# skematik_jppi.net
KiCad netlist of a schematic drawn in EAGLE
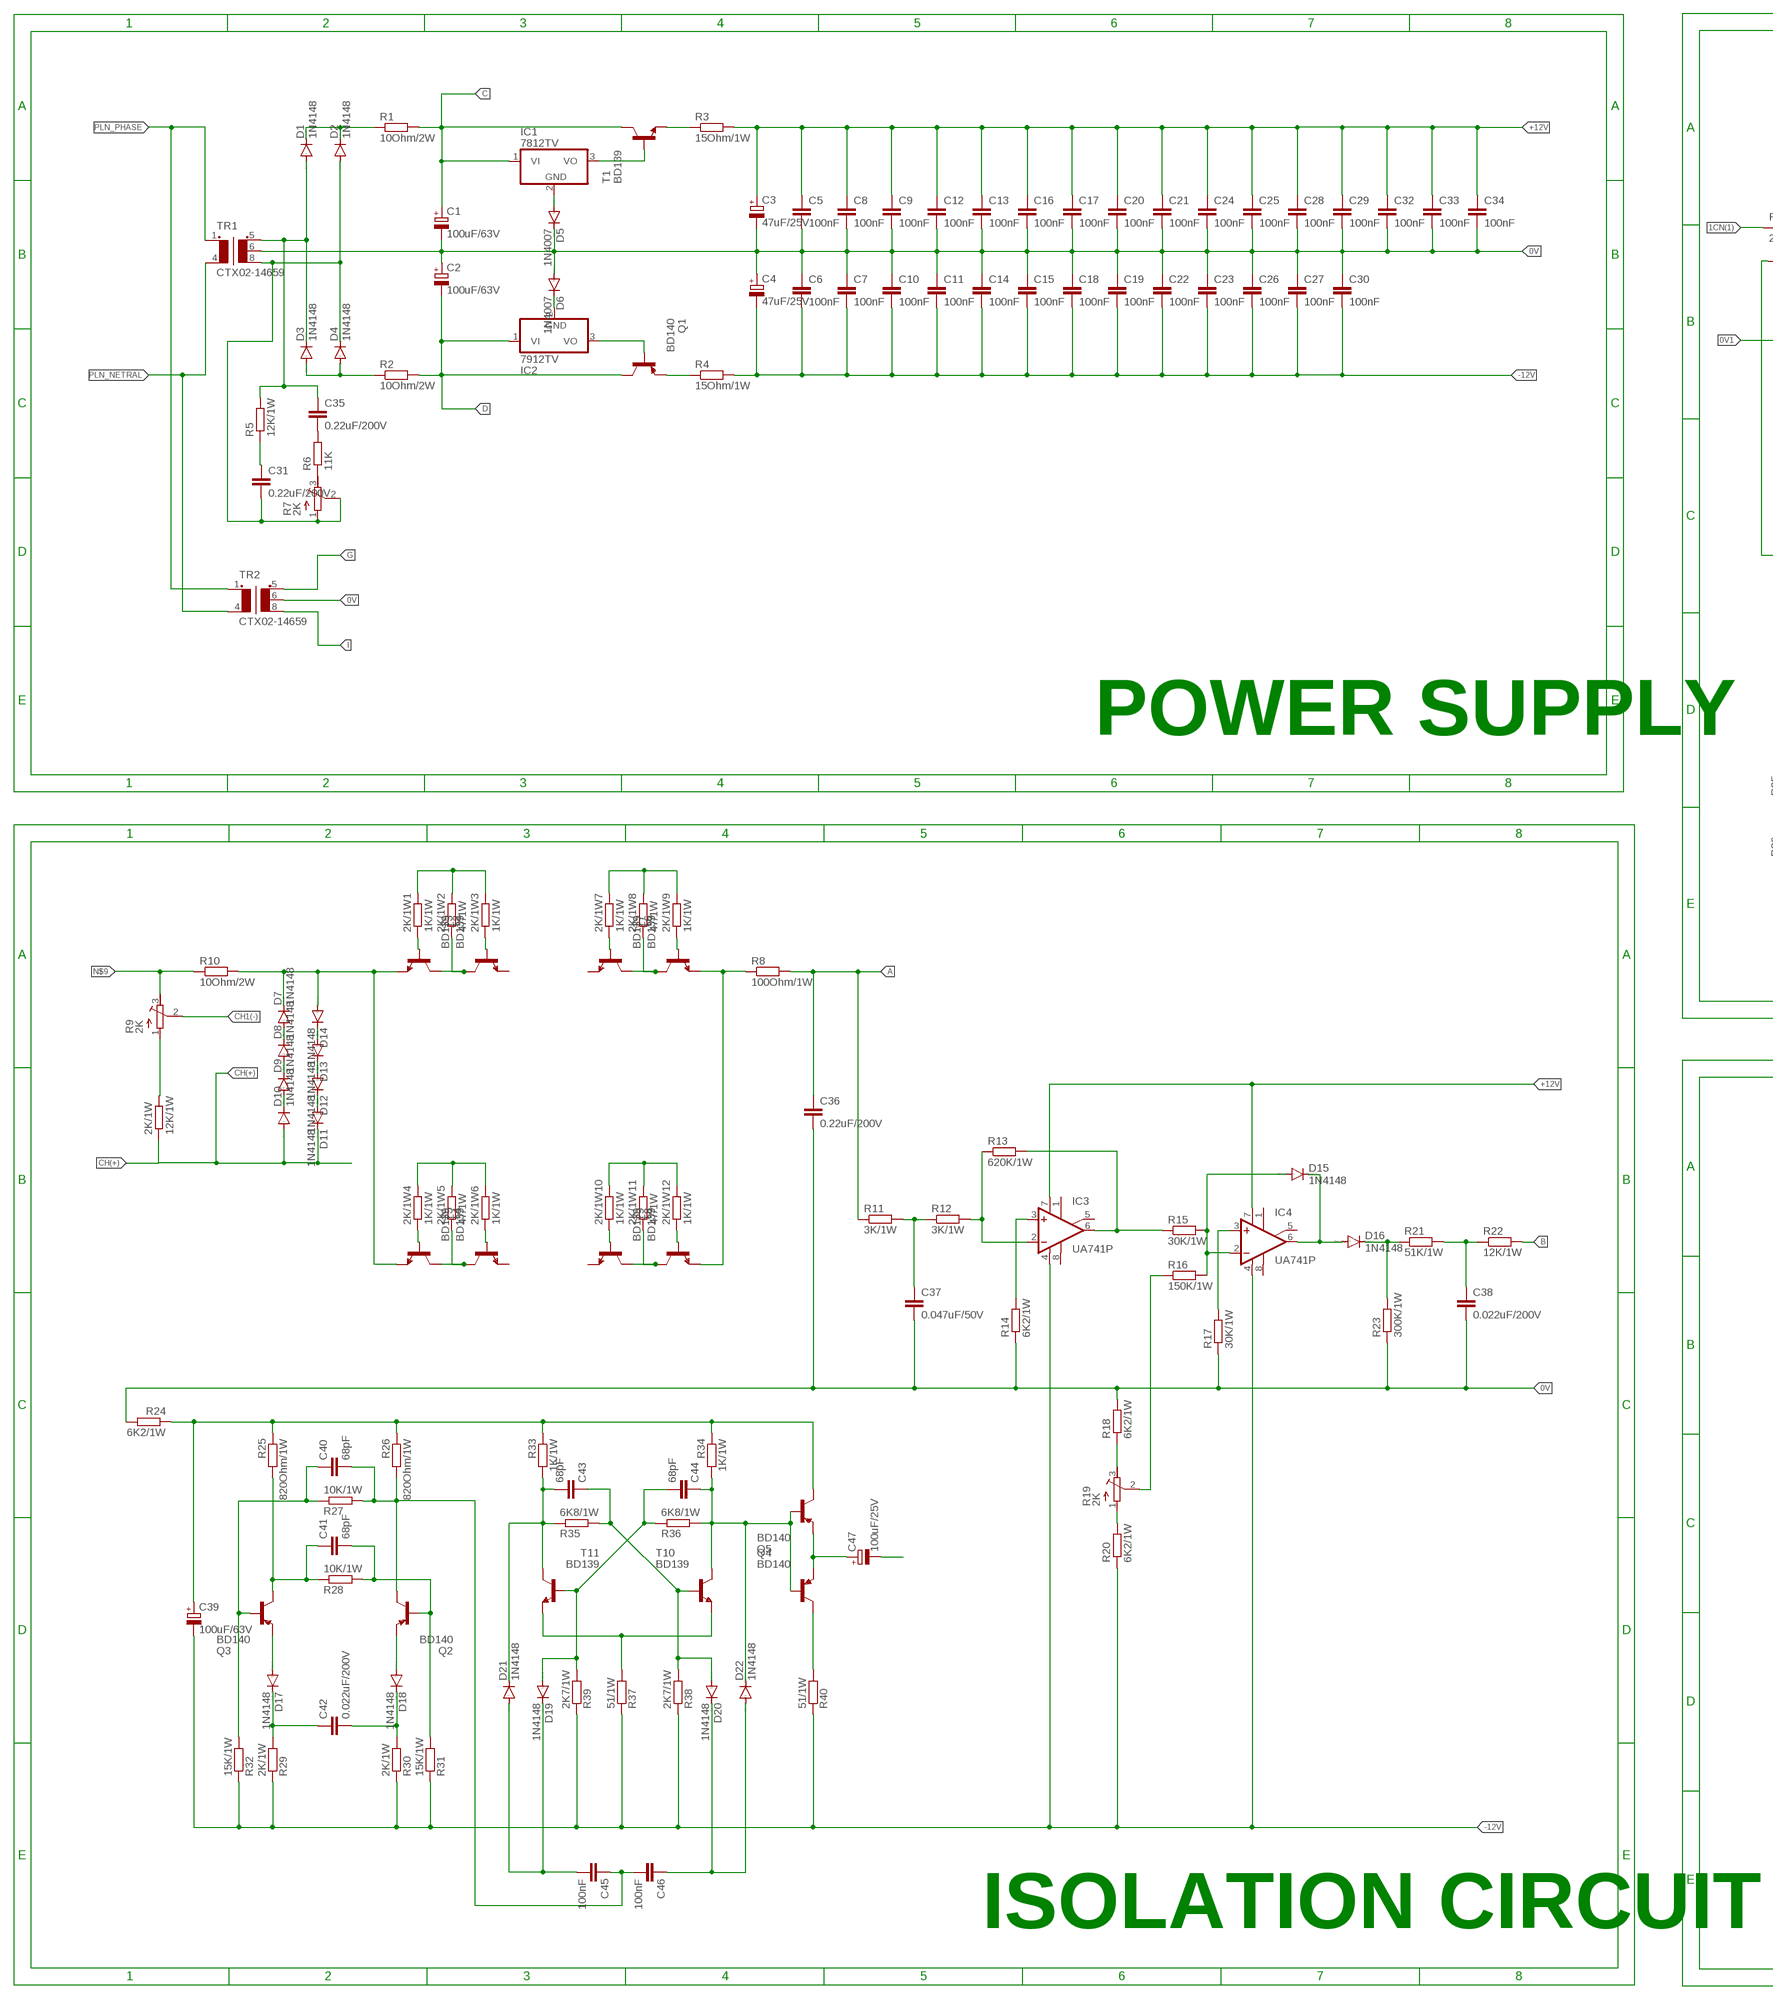
[diagram p0: schematic, sheet 1, part 1 of 3]
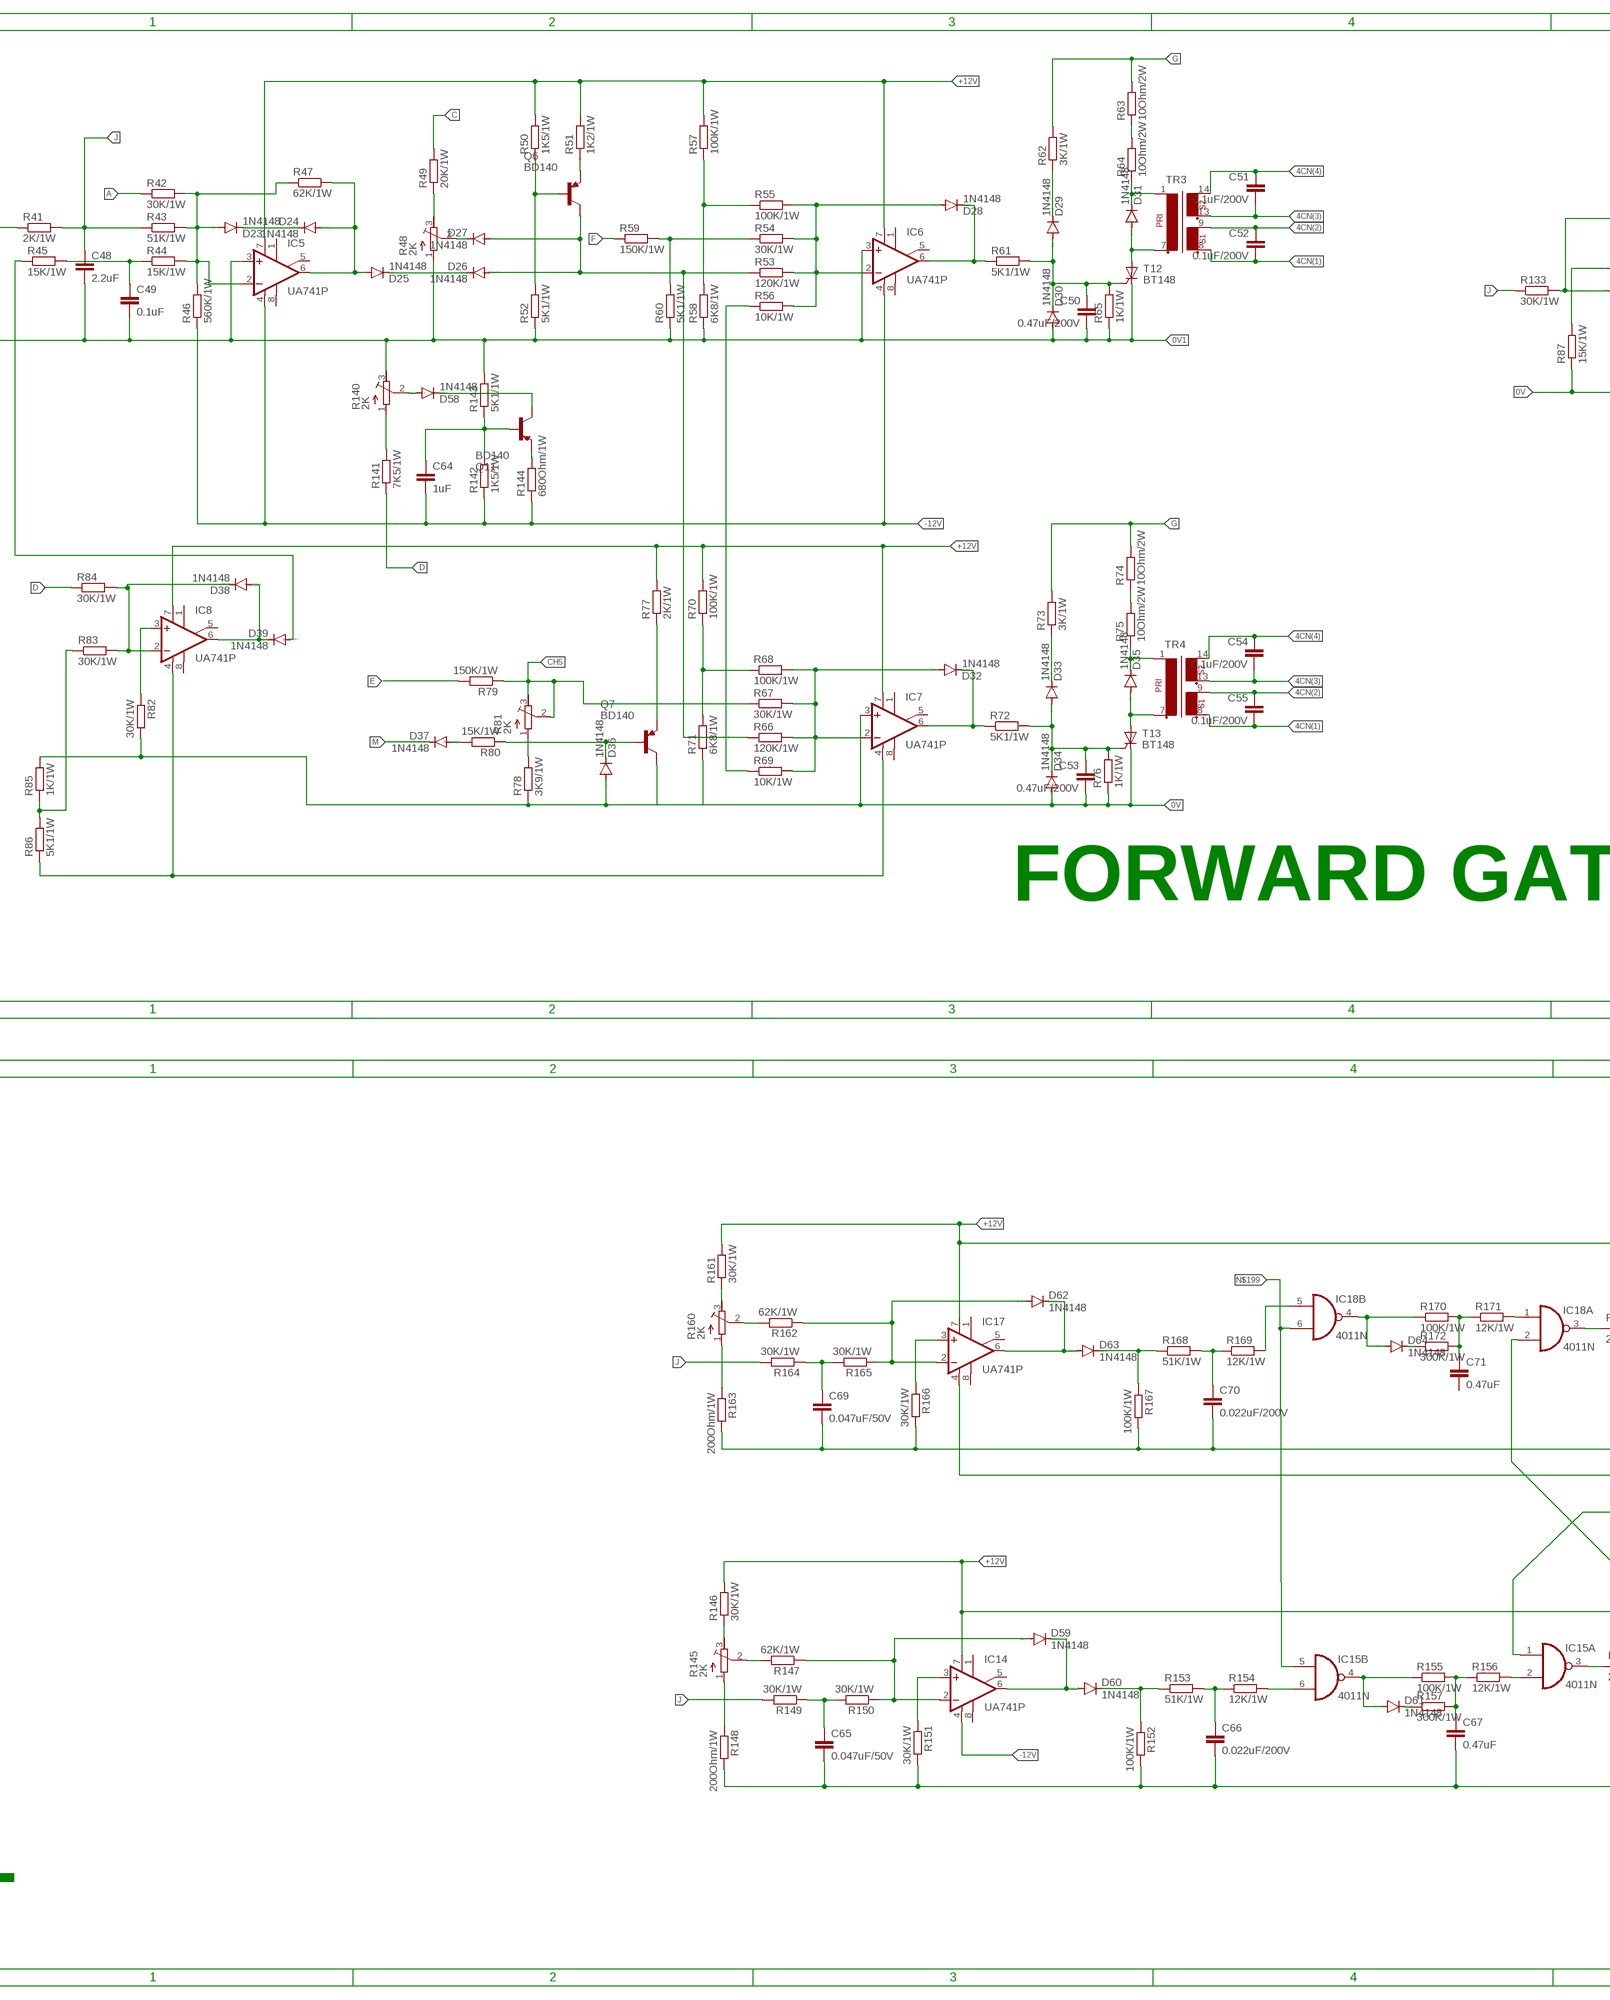
[diagram p1: schematic, sheet 1, part 2 of 3]
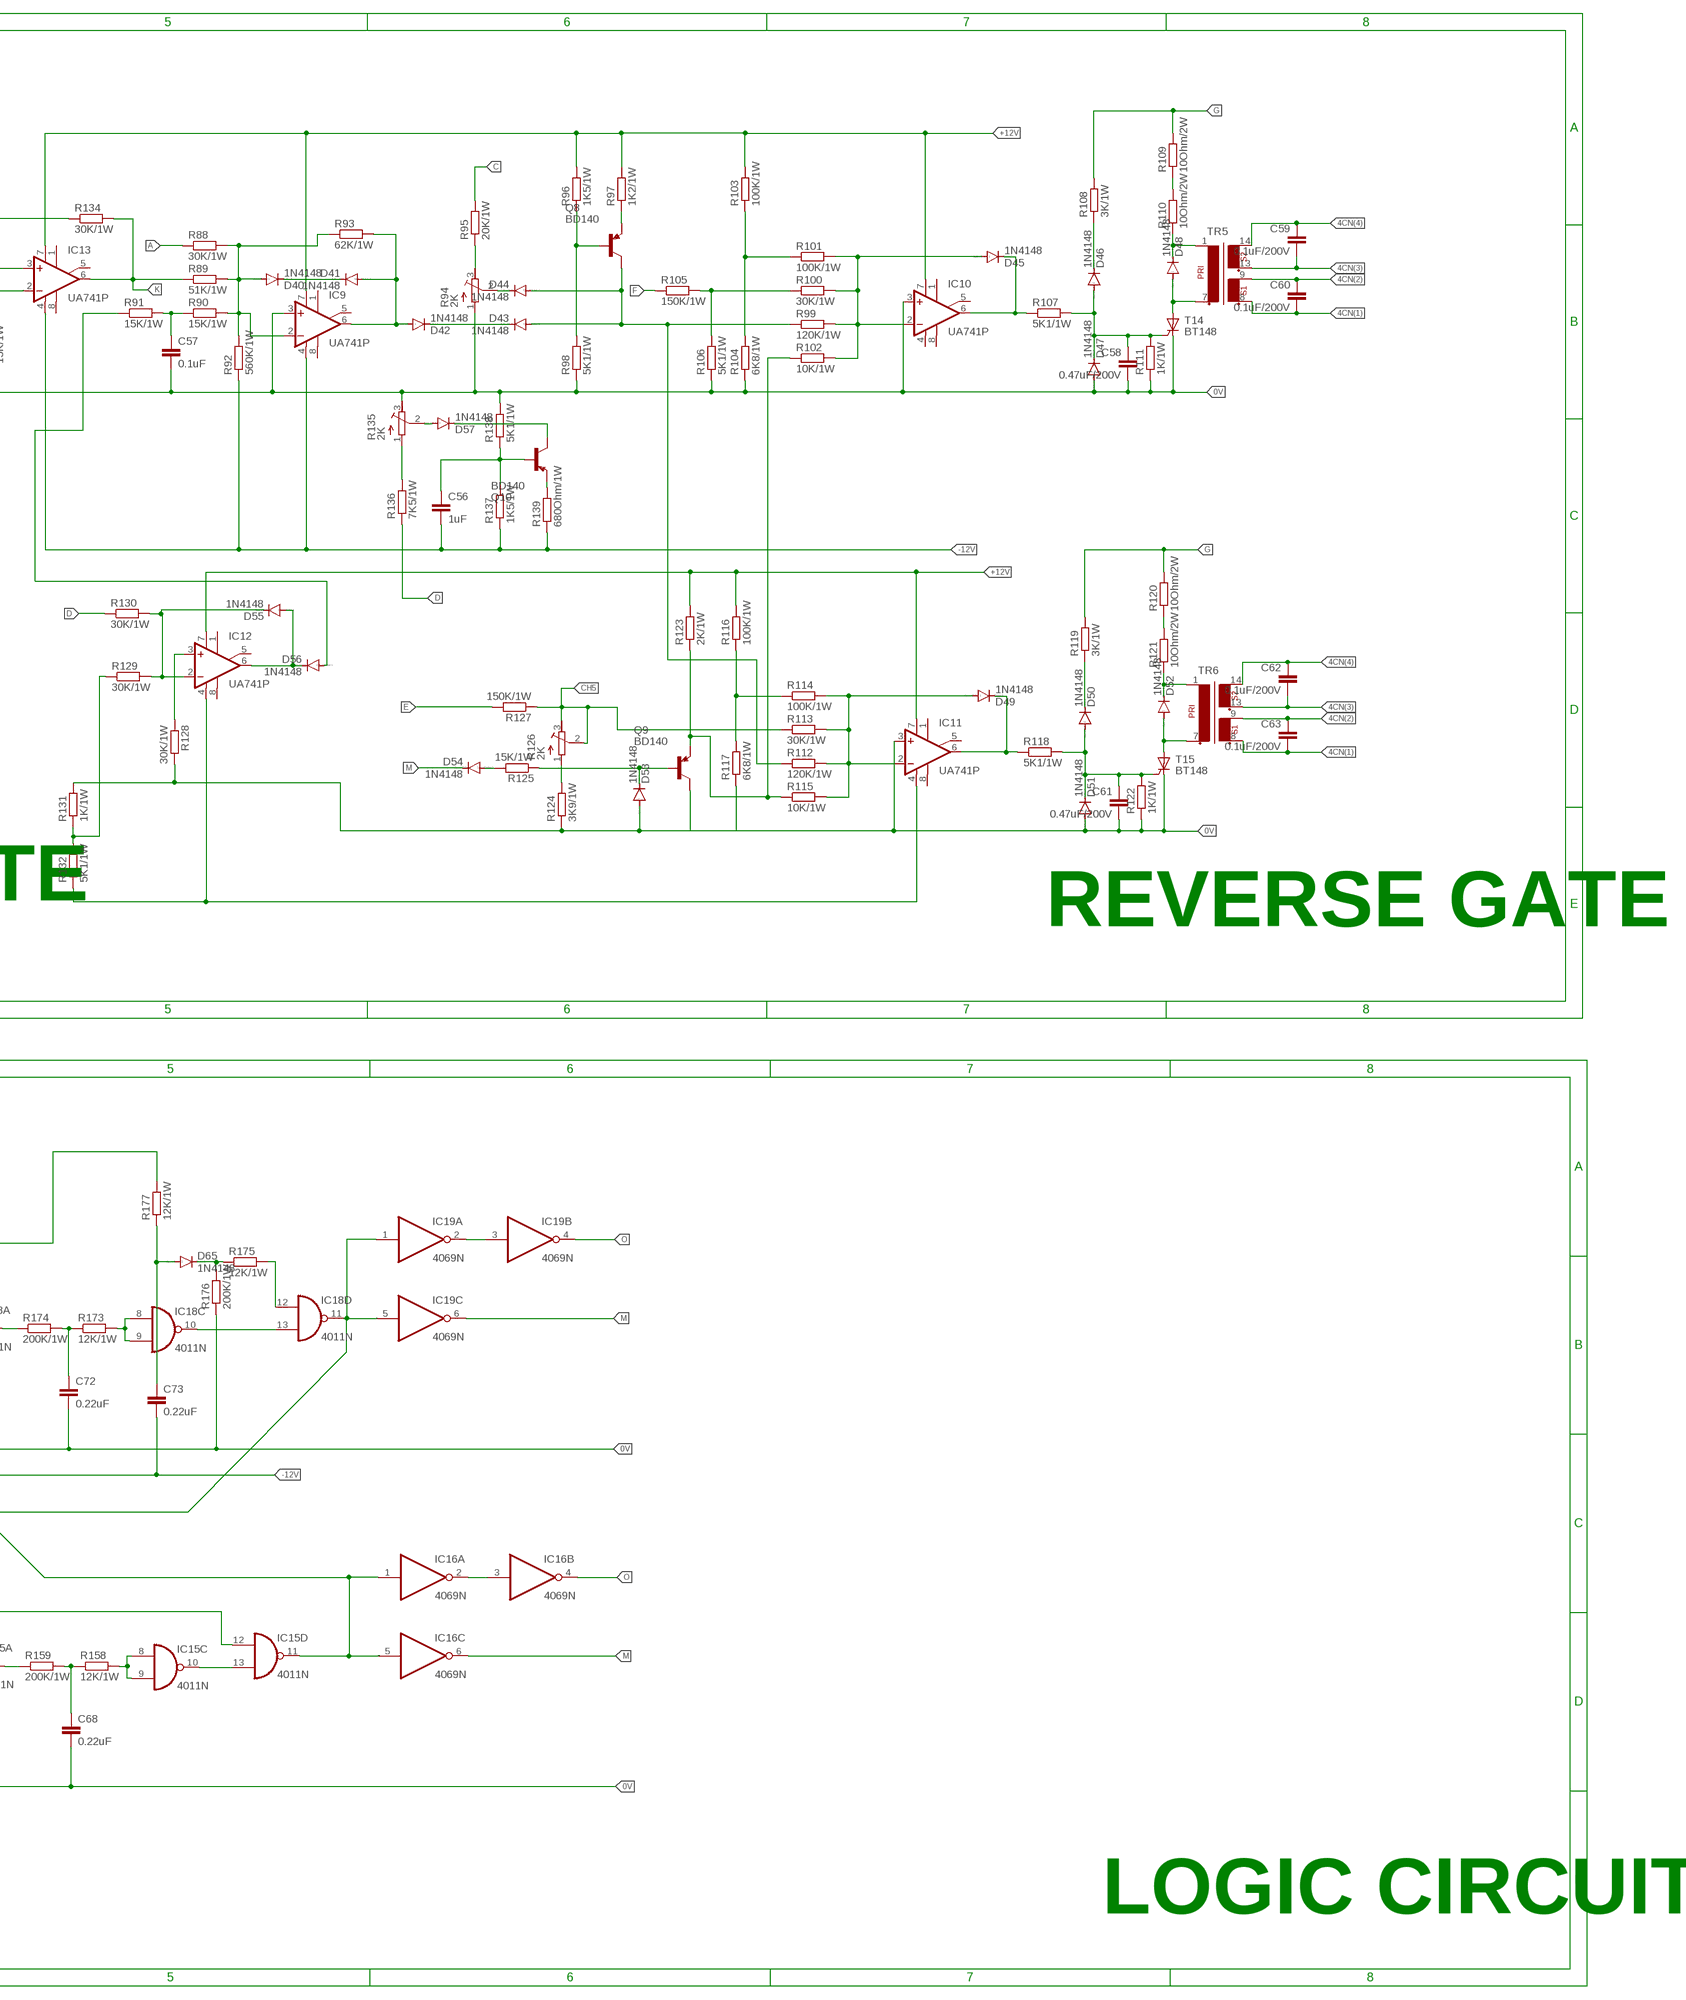
[diagram p2: schematic, sheet 1, part 3 of 3]

(export (version "E")
  (design (tool "Eeschema 10.0.6"))
  (components
    (comp (ref "2K/1W")
      (value "12K/1W")
      (footprint "eagle-import:0309_12")
      (libsource (lib "eagle-import") (part "R-EU_0309/12"))
    )
    (comp (ref "2K/1W1")
      (value "1K/1W")
      (footprint "eagle-import:0309_12")
      (libsource (lib "eagle-import") (part "R-EU_0309/12"))
    )
    (comp (ref "2K/1W2")
      (value "47/1W")
      (footprint "eagle-import:0309_12")
      (libsource (lib "eagle-import") (part "R-EU_0309/12"))
    )
    (comp (ref "2K/1W3")
      (value "1K/1W")
      (footprint "eagle-import:0309_12")
      (libsource (lib "eagle-import") (part "R-EU_0309/12"))
    )
    (comp (ref "2K/1W4")
      (value "1K/1W")
      (footprint "eagle-import:0309_12")
      (libsource (lib "eagle-import") (part "R-EU_0309/12"))
    )
    (comp (ref "2K/1W5")
      (value "47/1W")
      (footprint "eagle-import:0309_12")
      (libsource (lib "eagle-import") (part "R-EU_0309/12"))
    )
    (comp (ref "2K/1W6")
      (value "1K/1W")
      (footprint "eagle-import:0309_12")
      (libsource (lib "eagle-import") (part "R-EU_0309/12"))
    )
    (comp (ref "2K/1W7")
      (value "1K/1W")
      (footprint "eagle-import:0309_12")
      (libsource (lib "eagle-import") (part "R-EU_0309/12"))
    )
    (comp (ref "2K/1W8")
      (value "47/1W")
      (footprint "eagle-import:0309_12")
      (libsource (lib "eagle-import") (part "R-EU_0309/12"))
    )
    (comp (ref "2K/1W9")
      (value "1K/1W")
      (footprint "eagle-import:0309_12")
      (libsource (lib "eagle-import") (part "R-EU_0309/12"))
    )
    (comp (ref "2K/1W10")
      (value "1K/1W")
      (footprint "eagle-import:0309_12")
      (libsource (lib "eagle-import") (part "R-EU_0309/12"))
    )
    (comp (ref "2K/1W11")
      (value "47/1W")
      (footprint "eagle-import:0309_12")
      (libsource (lib "eagle-import") (part "R-EU_0309/12"))
    )
    (comp (ref "2K/1W12")
      (value "1K/1W")
      (footprint "eagle-import:0309_12")
      (libsource (lib "eagle-import") (part "R-EU_0309/12"))
    )
    (comp (ref "C1")
      (value "100uF/63V")
      (footprint "eagle-import:E5-10,5")
      (libsource (lib "eagle-import") (part "CPOL-EUE5-10.5"))
    )
    (comp (ref "C2")
      (value "100uF/63V")
      (footprint "eagle-import:E5-10,5")
      (libsource (lib "eagle-import") (part "CPOL-EUE5-10.5"))
    )
    (comp (ref "C3")
      (value "47uF/25V")
      (footprint "eagle-import:E5-10,5")
      (libsource (lib "eagle-import") (part "CPOL-EUE5-10.5"))
    )
    (comp (ref "C4")
      (value "47uF/25V")
      (footprint "eagle-import:E5-10,5")
      (libsource (lib "eagle-import") (part "CPOL-EUE5-10.5"))
    )
    (comp (ref "C5")
      (value "100nF")
      (footprint "eagle-import:C050-025X075")
      (libsource (lib "eagle-import") (part "C-EU050-025X075"))
    )
    (comp (ref "C6")
      (value "100nF")
      (footprint "eagle-import:C050-025X075")
      (libsource (lib "eagle-import") (part "C-EU050-025X075"))
    )
    (comp (ref "C7")
      (value "100nF")
      (footprint "eagle-import:C050-025X075")
      (libsource (lib "eagle-import") (part "C-EU050-025X075"))
    )
    (comp (ref "C8")
      (value "100nF")
      (footprint "eagle-import:C050-025X075")
      (libsource (lib "eagle-import") (part "C-EU050-025X075"))
    )
    (comp (ref "C9")
      (value "100nF")
      (footprint "eagle-import:C050-025X075")
      (libsource (lib "eagle-import") (part "C-EU050-025X075"))
    )
    (comp (ref "C10")
      (value "100nF")
      (footprint "eagle-import:C050-025X075")
      (libsource (lib "eagle-import") (part "C-EU050-025X075"))
    )
    (comp (ref "C11")
      (value "100nF")
      (footprint "eagle-import:C050-025X075")
      (libsource (lib "eagle-import") (part "C-EU050-025X075"))
    )
    (comp (ref "C12")
      (value "100nF")
      (footprint "eagle-import:C050-025X075")
      (libsource (lib "eagle-import") (part "C-EU050-025X075"))
    )
    (comp (ref "C13")
      (value "100nF")
      (footprint "eagle-import:C050-025X075")
      (libsource (lib "eagle-import") (part "C-EU050-025X075"))
    )
    (comp (ref "C14")
      (value "100nF")
      (footprint "eagle-import:C050-025X075")
      (libsource (lib "eagle-import") (part "C-EU050-025X075"))
    )
    (comp (ref "C15")
      (value "100nF")
      (footprint "eagle-import:C050-025X075")
      (libsource (lib "eagle-import") (part "C-EU050-025X075"))
    )
    (comp (ref "C16")
      (value "100nF")
      (footprint "eagle-import:C050-025X075")
      (libsource (lib "eagle-import") (part "C-EU050-025X075"))
    )
    (comp (ref "C17")
      (value "100nF")
      (footprint "eagle-import:C050-025X075")
      (libsource (lib "eagle-import") (part "C-EU050-025X075"))
    )
    (comp (ref "C18")
      (value "100nF")
      (footprint "eagle-import:C050-025X075")
      (libsource (lib "eagle-import") (part "C-EU050-025X075"))
    )
    (comp (ref "C19")
      (value "100nF")
      (footprint "eagle-import:C050-025X075")
      (libsource (lib "eagle-import") (part "C-EU050-025X075"))
    )
    (comp (ref "C20")
      (value "100nF")
      (footprint "eagle-import:C050-025X075")
      (libsource (lib "eagle-import") (part "C-EU050-025X075"))
    )
    (comp (ref "C21")
      (value "100nF")
      (footprint "eagle-import:C050-025X075")
      (libsource (lib "eagle-import") (part "C-EU050-025X075"))
    )
    (comp (ref "C22")
      (value "100nF")
      (footprint "eagle-import:C050-025X075")
      (libsource (lib "eagle-import") (part "C-EU050-025X075"))
    )
    (comp (ref "C23")
      (value "100nF")
      (footprint "eagle-import:C050-025X075")
      (libsource (lib "eagle-import") (part "C-EU050-025X075"))
    )
    (comp (ref "C24")
      (value "100nF")
      (footprint "eagle-import:C050-025X075")
      (libsource (lib "eagle-import") (part "C-EU050-025X075"))
    )
    (comp (ref "C25")
      (value "100nF")
      (footprint "eagle-import:C050-025X075")
      (libsource (lib "eagle-import") (part "C-EU050-025X075"))
    )
    (comp (ref "C26")
      (value "100nF")
      (footprint "eagle-import:C050-025X075")
      (libsource (lib "eagle-import") (part "C-EU050-025X075"))
    )
    (comp (ref "C27")
      (value "100nF")
      (footprint "eagle-import:C050-025X075")
      (libsource (lib "eagle-import") (part "C-EU050-025X075"))
    )
    (comp (ref "C28")
      (value "100nF")
      (footprint "eagle-import:C050-025X075")
      (libsource (lib "eagle-import") (part "C-EU050-025X075"))
    )
    (comp (ref "C29")
      (value "100nF")
      (footprint "eagle-import:C050-025X075")
      (libsource (lib "eagle-import") (part "C-EU050-025X075"))
    )
    (comp (ref "C30")
      (value "100nF")
      (footprint "eagle-import:C050-025X075")
      (libsource (lib "eagle-import") (part "C-EU050-025X075"))
    )
    (comp (ref "C31")
      (value "0.22uF/200V")
      (footprint "eagle-import:C102-043X133")
      (libsource (lib "eagle-import") (part "C-EU102-043X133"))
    )
    (comp (ref "C32")
      (value "100nF")
      (footprint "eagle-import:C050-025X075")
      (libsource (lib "eagle-import") (part "C-EU050-025X075"))
    )
    (comp (ref "C33")
      (value "100nF")
      (footprint "eagle-import:C050-025X075")
      (libsource (lib "eagle-import") (part "C-EU050-025X075"))
    )
    (comp (ref "C34")
      (value "100nF")
      (footprint "eagle-import:C050-025X075")
      (libsource (lib "eagle-import") (part "C-EU050-025X075"))
    )
    (comp (ref "C35")
      (value "0.22uF/200V")
      (footprint "eagle-import:C102-043X133")
      (libsource (lib "eagle-import") (part "C-EU102-043X133"))
    )
    (comp (ref "C36")
      (value "0.22uF/200V")
      (footprint "eagle-import:C102-043X133")
      (libsource (lib "eagle-import") (part "C-EU102-043X133"))
    )
    (comp (ref "C37")
      (value "0.047uF/50V")
      (footprint "eagle-import:C075-032X103")
      (libsource (lib "eagle-import") (part "C-EU075-032X103"))
    )
    (comp (ref "C38")
      (value "0.022uF/200V")
      (footprint "eagle-import:C102-043X133")
      (libsource (lib "eagle-import") (part "C-EU102-043X133"))
    )
    (comp (ref "C39")
      (value "100uF/63V")
      (footprint "eagle-import:E5-10,5")
      (libsource (lib "eagle-import") (part "CPOL-EUE5-10.5"))
    )
    (comp (ref "C40")
      (value "68pF")
      (footprint "eagle-import:C050-024X044")
      (libsource (lib "eagle-import") (part "C-EU050-024X044"))
    )
    (comp (ref "C41")
      (value "68pF")
      (footprint "eagle-import:C050-024X044")
      (libsource (lib "eagle-import") (part "C-EU050-024X044"))
    )
    (comp (ref "C42")
      (value "0.022uF/200V")
      (footprint "eagle-import:C102-043X133")
      (libsource (lib "eagle-import") (part "C-EU102-043X133"))
    )
    (comp (ref "C43")
      (value "68pF")
      (footprint "eagle-import:C050-024X044")
      (libsource (lib "eagle-import") (part "C-EU050-024X044"))
    )
    (comp (ref "C44")
      (value "68pF")
      (footprint "eagle-import:C050-024X044")
      (libsource (lib "eagle-import") (part "C-EU050-024X044"))
    )
    (comp (ref "C45")
      (value "100nF")
      (footprint "eagle-import:C050-025X075")
      (libsource (lib "eagle-import") (part "C-EU050-025X075"))
    )
    (comp (ref "C46")
      (value "100nF")
      (footprint "eagle-import:C050-025X075")
      (libsource (lib "eagle-import") (part "C-EU050-025X075"))
    )
    (comp (ref "C47")
      (value "100uF/25V")
      (footprint "eagle-import:E5-10,5")
      (libsource (lib "eagle-import") (part "CPOL-EUE5-10.5"))
    )
    (comp (ref "C48")
      (value "2.2uF")
      (footprint "eagle-import:C050-025X075")
      (libsource (lib "eagle-import") (part "C-EU050-025X075"))
    )
    (comp (ref "C49")
      (value "0.1uF")
      (footprint "eagle-import:C050-025X075")
      (libsource (lib "eagle-import") (part "C-EU050-025X075"))
    )
    (comp (ref "C50")
      (value "0.47uF/200V")
      (footprint "eagle-import:C102-043X133")
      (libsource (lib "eagle-import") (part "C-EU102-043X133"))
    )
    (comp (ref "C51")
      (value "0.1uF/200V")
      (footprint "eagle-import:C102-043X133")
      (libsource (lib "eagle-import") (part "C-EU102-043X133"))
    )
    (comp (ref "C52")
      (value "0.1uF/200V")
      (footprint "eagle-import:C102-043X133")
      (libsource (lib "eagle-import") (part "C-EU102-043X133"))
    )
    (comp (ref "C53")
      (value "0.47uF/200V")
      (footprint "eagle-import:C102-043X133")
      (libsource (lib "eagle-import") (part "C-EU102-043X133"))
    )
    (comp (ref "C54")
      (value "0.1uF/200V")
      (footprint "eagle-import:C102-043X133")
      (libsource (lib "eagle-import") (part "C-EU102-043X133"))
    )
    (comp (ref "C55")
      (value "0.1uF/200V")
      (footprint "eagle-import:C102-043X133")
      (libsource (lib "eagle-import") (part "C-EU102-043X133"))
    )
    (comp (ref "C56")
      (value "1uF")
      (footprint "eagle-import:C050-025X075")
      (libsource (lib "eagle-import") (part "C-EU050-025X075"))
    )
    (comp (ref "C57")
      (value "0.1uF")
      (footprint "eagle-import:C050-025X075")
      (libsource (lib "eagle-import") (part "C-EU050-025X075"))
    )
    (comp (ref "C58")
      (value "0.47uF/200V")
      (footprint "eagle-import:C102-043X133")
      (libsource (lib "eagle-import") (part "C-EU102-043X133"))
    )
    (comp (ref "C59")
      (value "0.1uF/200V")
      (footprint "eagle-import:C102-043X133")
      (libsource (lib "eagle-import") (part "C-EU102-043X133"))
    )
    (comp (ref "C60")
      (value "0.1uF/200V")
      (footprint "eagle-import:C102-043X133")
      (libsource (lib "eagle-import") (part "C-EU102-043X133"))
    )
    (comp (ref "C61")
      (value "0.47uF/200V")
      (footprint "eagle-import:C102-043X133")
      (libsource (lib "eagle-import") (part "C-EU102-043X133"))
    )
    (comp (ref "C62")
      (value "0.1uF/200V")
      (footprint "eagle-import:C102-043X133")
      (libsource (lib "eagle-import") (part "C-EU102-043X133"))
    )
    (comp (ref "C63")
      (value "0.1uF/200V")
      (footprint "eagle-import:C102-043X133")
      (libsource (lib "eagle-import") (part "C-EU102-043X133"))
    )
    (comp (ref "C64")
      (value "1uF")
      (footprint "eagle-import:C050-025X075")
      (libsource (lib "eagle-import") (part "C-EU050-025X075"))
    )
    (comp (ref "C65")
      (value "0.047uF/50V")
      (footprint "eagle-import:C102-043X133")
      (libsource (lib "eagle-import") (part "C-EU102-043X133"))
    )
    (comp (ref "C66")
      (value "0.022uF/200V")
      (footprint "eagle-import:C102-043X133")
      (libsource (lib "eagle-import") (part "C-EU102-043X133"))
    )
    (comp (ref "C67")
      (value "0.47uF")
      (footprint "eagle-import:C102-043X133")
      (libsource (lib "eagle-import") (part "C-EU102-043X133"))
    )
    (comp (ref "C68")
      (value "0.22uF")
      (footprint "eagle-import:C102-043X133")
      (libsource (lib "eagle-import") (part "C-EU102-043X133"))
    )
    (comp (ref "C69")
      (value "0.047uF/50V")
      (footprint "eagle-import:C102-043X133")
      (libsource (lib "eagle-import") (part "C-EU102-043X133"))
    )
    (comp (ref "C70")
      (value "0.022uF/200V")
      (footprint "eagle-import:C102-043X133")
      (libsource (lib "eagle-import") (part "C-EU102-043X133"))
    )
    (comp (ref "C71")
      (value "0.47uF")
      (footprint "eagle-import:C102-043X133")
      (libsource (lib "eagle-import") (part "C-EU102-043X133"))
    )
    (comp (ref "C72")
      (value "0.22uF")
      (footprint "eagle-import:C102-043X133")
      (libsource (lib "eagle-import") (part "C-EU102-043X133"))
    )
    (comp (ref "C73")
      (value "0.22uF")
      (footprint "eagle-import:C102-043X133")
      (libsource (lib "eagle-import") (part "C-EU102-043X133"))
    )
    (comp (ref "D1")
      (value "1N4148")
      (footprint "eagle-import:DO41-10")
      (libsource (lib "eagle-import") (part "1N4004"))
    )
    (comp (ref "D2")
      (value "1N4148")
      (footprint "eagle-import:DO41-10")
      (libsource (lib "eagle-import") (part "1N4004"))
    )
    (comp (ref "D3")
      (value "1N4148")
      (footprint "eagle-import:DO41-10")
      (libsource (lib "eagle-import") (part "1N4004"))
    )
    (comp (ref "D4")
      (value "1N4148")
      (footprint "eagle-import:DO41-10")
      (libsource (lib "eagle-import") (part "1N4004"))
    )
    (comp (ref "D5")
      (value "1N4007")
      (footprint "eagle-import:DO41-10")
      (libsource (lib "eagle-import") (part "1N4004"))
    )
    (comp (ref "D6")
      (value "1N4007")
      (footprint "eagle-import:DO41-10")
      (libsource (lib "eagle-import") (part "1N4004"))
    )
    (comp (ref "D7")
      (value "1N4148")
      (footprint "eagle-import:DO41-10")
      (libsource (lib "eagle-import") (part "1N4004"))
    )
    (comp (ref "D8")
      (value "1N4148")
      (footprint "eagle-import:DO41-10")
      (libsource (lib "eagle-import") (part "1N4004"))
    )
    (comp (ref "D9")
      (value "1N4148")
      (footprint "eagle-import:DO41-10")
      (libsource (lib "eagle-import") (part "1N4004"))
    )
    (comp (ref "D10")
      (value "1N4148")
      (footprint "eagle-import:DO41-10")
      (libsource (lib "eagle-import") (part "1N4004"))
    )
    (comp (ref "D11")
      (value "1N4148")
      (footprint "eagle-import:DO41-10")
      (libsource (lib "eagle-import") (part "1N4004"))
    )
    (comp (ref "D12")
      (value "1N4148")
      (footprint "eagle-import:DO41-10")
      (libsource (lib "eagle-import") (part "1N4004"))
    )
    (comp (ref "D13")
      (value "1N4148")
      (footprint "eagle-import:DO41-10")
      (libsource (lib "eagle-import") (part "1N4004"))
    )
    (comp (ref "D14")
      (value "1N4148")
      (footprint "eagle-import:DO41-10")
      (libsource (lib "eagle-import") (part "1N4004"))
    )
    (comp (ref "D15")
      (value "1N4148")
      (footprint "eagle-import:DO41-10")
      (libsource (lib "eagle-import") (part "1N4004"))
    )
    (comp (ref "D16")
      (value "1N4148")
      (footprint "eagle-import:DO41-10")
      (libsource (lib "eagle-import") (part "1N4004"))
    )
    (comp (ref "D17")
      (value "1N4148")
      (footprint "eagle-import:DO41-10")
      (libsource (lib "eagle-import") (part "1N4004"))
    )
    (comp (ref "D18")
      (value "1N4148")
      (footprint "eagle-import:DO41-10")
      (libsource (lib "eagle-import") (part "1N4004"))
    )
    (comp (ref "D19")
      (value "1N4148")
      (footprint "eagle-import:DO41-10")
      (libsource (lib "eagle-import") (part "1N4004"))
    )
    (comp (ref "D20")
      (value "1N4148")
      (footprint "eagle-import:DO41-10")
      (libsource (lib "eagle-import") (part "1N4004"))
    )
    (comp (ref "D21")
      (value "1N4148")
      (footprint "eagle-import:DO41-10")
      (libsource (lib "eagle-import") (part "1N4004"))
    )
    (comp (ref "D22")
      (value "1N4148")
      (footprint "eagle-import:DO41-10")
      (libsource (lib "eagle-import") (part "1N4004"))
    )
    (comp (ref "D23")
      (value "1N4148")
      (footprint "eagle-import:DO41-10")
      (libsource (lib "eagle-import") (part "1N4004"))
    )
    (comp (ref "D24")
      (value "1N4148")
      (footprint "eagle-import:DO41-10")
      (libsource (lib "eagle-import") (part "1N4004"))
    )
    (comp (ref "D25")
      (value "1N4148")
      (footprint "eagle-import:DO41-10")
      (libsource (lib "eagle-import") (part "1N4004"))
    )
    (comp (ref "D26")
      (value "1N4148")
      (footprint "eagle-import:DO41-10")
      (libsource (lib "eagle-import") (part "1N4004"))
    )
    (comp (ref "D27")
      (value "1N4148")
      (footprint "eagle-import:DO41-10")
      (libsource (lib "eagle-import") (part "1N4004"))
    )
    (comp (ref "D28")
      (value "1N4148")
      (footprint "eagle-import:DO41-10")
      (libsource (lib "eagle-import") (part "1N4004"))
    )
    (comp (ref "D29")
      (value "1N4148")
      (footprint "eagle-import:DO41-10")
      (libsource (lib "eagle-import") (part "1N4004"))
    )
    (comp (ref "D30")
      (value "1N4148")
      (footprint "eagle-import:DO41-10")
      (libsource (lib "eagle-import") (part "1N4004"))
    )
    (comp (ref "D31")
      (value "1N4148")
      (footprint "eagle-import:DO41-10")
      (libsource (lib "eagle-import") (part "1N4004"))
    )
    (comp (ref "D32")
      (value "1N4148")
      (footprint "eagle-import:DO41-10")
      (libsource (lib "eagle-import") (part "1N4004"))
    )
    (comp (ref "D33")
      (value "1N4148")
      (footprint "eagle-import:DO41-10")
      (libsource (lib "eagle-import") (part "1N4004"))
    )
    (comp (ref "D34")
      (value "1N4148")
      (footprint "eagle-import:DO41-10")
      (libsource (lib "eagle-import") (part "1N4004"))
    )
    (comp (ref "D35")
      (value "1N4148")
      (footprint "eagle-import:DO41-10")
      (libsource (lib "eagle-import") (part "1N4004"))
    )
    (comp (ref "D36")
      (value "1N4148")
      (footprint "eagle-import:DO41-10")
      (libsource (lib "eagle-import") (part "1N4004"))
    )
    (comp (ref "D37")
      (value "1N4148")
      (footprint "eagle-import:DO41-10")
      (libsource (lib "eagle-import") (part "1N4004"))
    )
    (comp (ref "D38")
      (value "1N4148")
      (footprint "eagle-import:DO41-10")
      (libsource (lib "eagle-import") (part "1N4004"))
    )
    (comp (ref "D39")
      (value "1N4148")
      (footprint "eagle-import:DO41-10")
      (libsource (lib "eagle-import") (part "1N4004"))
    )
    (comp (ref "D40")
      (value "1N4148")
      (footprint "eagle-import:DO41-10")
      (libsource (lib "eagle-import") (part "1N4004"))
    )
    (comp (ref "D41")
      (value "1N4148")
      (footprint "eagle-import:DO41-10")
      (libsource (lib "eagle-import") (part "1N4004"))
    )
    (comp (ref "D42")
      (value "1N4148")
      (footprint "eagle-import:DO41-10")
      (libsource (lib "eagle-import") (part "1N4004"))
    )
    (comp (ref "D43")
      (value "1N4148")
      (footprint "eagle-import:DO41-10")
      (libsource (lib "eagle-import") (part "1N4004"))
    )
    (comp (ref "D44")
      (value "1N4148")
      (footprint "eagle-import:DO41-10")
      (libsource (lib "eagle-import") (part "1N4004"))
    )
    (comp (ref "D45")
      (value "1N4148")
      (footprint "eagle-import:DO41-10")
      (libsource (lib "eagle-import") (part "1N4004"))
    )
    (comp (ref "D46")
      (value "1N4148")
      (footprint "eagle-import:DO41-10")
      (libsource (lib "eagle-import") (part "1N4004"))
    )
    (comp (ref "D47")
      (value "1N4148")
      (footprint "eagle-import:DO41-10")
      (libsource (lib "eagle-import") (part "1N4004"))
    )
    (comp (ref "D48")
      (value "1N4148")
      (footprint "eagle-import:DO41-10")
      (libsource (lib "eagle-import") (part "1N4004"))
    )
    (comp (ref "D49")
      (value "1N4148")
      (footprint "eagle-import:DO41-10")
      (libsource (lib "eagle-import") (part "1N4004"))
    )
    (comp (ref "D50")
      (value "1N4148")
      (footprint "eagle-import:DO41-10")
      (libsource (lib "eagle-import") (part "1N4004"))
    )
    (comp (ref "D51")
      (value "1N4148")
      (footprint "eagle-import:DO41-10")
      (libsource (lib "eagle-import") (part "1N4004"))
    )
    (comp (ref "D52")
      (value "1N4148")
      (footprint "eagle-import:DO41-10")
      (libsource (lib "eagle-import") (part "1N4004"))
    )
    (comp (ref "D53")
      (value "1N4148")
      (footprint "eagle-import:DO41-10")
      (libsource (lib "eagle-import") (part "1N4004"))
    )
    (comp (ref "D54")
      (value "1N4148")
      (footprint "eagle-import:DO41-10")
      (libsource (lib "eagle-import") (part "1N4004"))
    )
    (comp (ref "D55")
      (value "1N4148")
      (footprint "eagle-import:DO41-10")
      (libsource (lib "eagle-import") (part "1N4004"))
    )
    (comp (ref "D56")
      (value "1N4148")
      (footprint "eagle-import:DO41-10")
      (libsource (lib "eagle-import") (part "1N4004"))
    )
    (comp (ref "D57")
      (value "1N4148")
      (footprint "eagle-import:DO41-10")
      (libsource (lib "eagle-import") (part "1N4004"))
    )
    (comp (ref "D58")
      (value "1N4148")
      (footprint "eagle-import:DO41-10")
      (libsource (lib "eagle-import") (part "1N4004"))
    )
    (comp (ref "D59")
      (value "1N4148")
      (footprint "eagle-import:DO41-10")
      (libsource (lib "eagle-import") (part "1N4004"))
    )
    (comp (ref "D60")
      (value "1N4148")
      (footprint "eagle-import:DO41-10")
      (libsource (lib "eagle-import") (part "1N4004"))
    )
    (comp (ref "D61")
      (value "1N4148")
      (footprint "eagle-import:DO41-10")
      (libsource (lib "eagle-import") (part "1N4004"))
    )
    (comp (ref "D62")
      (value "1N4148")
      (footprint "eagle-import:DO41-10")
      (libsource (lib "eagle-import") (part "1N4004"))
    )
    (comp (ref "D63")
      (value "1N4148")
      (footprint "eagle-import:DO41-10")
      (libsource (lib "eagle-import") (part "1N4004"))
    )
    (comp (ref "D64")
      (value "1N4148")
      (footprint "eagle-import:DO41-10")
      (libsource (lib "eagle-import") (part "1N4004"))
    )
    (comp (ref "D65")
      (value "1N4148")
      (footprint "eagle-import:DO41-10")
      (libsource (lib "eagle-import") (part "1N4004"))
    )
    (comp (ref "IC1")
      (value "7812TV")
      (footprint "eagle-import:TO220V")
      (libsource (lib "eagle-import") (part "78TV12"))
    )
    (comp (ref "IC2")
      (value "7912TV")
      (footprint "eagle-import:TO220V")
      (libsource (lib "eagle-import") (part "78TV12"))
    )
    (comp (ref "IC3")
      (value "UA741P")
      (footprint "eagle-import:DIL08")
      (libsource (lib "eagle-import") (part "741PUA"))
    )
    (comp (ref "IC4")
      (value "UA741P")
      (footprint "eagle-import:DIL08")
      (libsource (lib "eagle-import") (part "741PUA"))
    )
    (comp (ref "IC5")
      (value "UA741P")
      (footprint "eagle-import:DIL08")
      (libsource (lib "eagle-import") (part "741PUA"))
    )
    (comp (ref "IC6")
      (value "UA741P")
      (footprint "eagle-import:DIL08")
      (libsource (lib "eagle-import") (part "741PUA"))
    )
    (comp (ref "IC7")
      (value "UA741P")
      (footprint "eagle-import:DIL08")
      (libsource (lib "eagle-import") (part "741PUA"))
    )
    (comp (ref "IC8")
      (value "UA741P")
      (footprint "eagle-import:DIL08")
      (libsource (lib "eagle-import") (part "741PUA"))
    )
    (comp (ref "IC9")
      (value "UA741P")
      (footprint "eagle-import:DIL08")
      (libsource (lib "eagle-import") (part "741PUA"))
    )
    (comp (ref "IC10")
      (value "UA741P")
      (footprint "eagle-import:DIL08")
      (libsource (lib "eagle-import") (part "741PUA"))
    )
    (comp (ref "IC11")
      (value "UA741P")
      (footprint "eagle-import:DIL08")
      (libsource (lib "eagle-import") (part "741PUA"))
    )
    (comp (ref "IC12")
      (value "UA741P")
      (footprint "eagle-import:DIL08")
      (libsource (lib "eagle-import") (part "741PUA"))
    )
    (comp (ref "IC13")
      (value "UA741P")
      (footprint "eagle-import:DIL08")
      (libsource (lib "eagle-import") (part "741PUA"))
    )
    (comp (ref "IC14")
      (value "UA741P")
      (footprint "eagle-import:DIL08")
      (libsource (lib "eagle-import") (part "741PUA"))
    )
    (comp (ref "IC15")
      (value "4011N")
      (footprint "eagle-import:DIL14")
      (libsource (lib "eagle-import") (part "4011N"))
    )
    (comp (ref "IC16")
      (value "4069N")
      (footprint "eagle-import:DIL14")
      (libsource (lib "eagle-import") (part "4069N"))
    )
    (comp (ref "IC17")
      (value "UA741P")
      (footprint "eagle-import:DIL08")
      (libsource (lib "eagle-import") (part "741PUA"))
    )
    (comp (ref "IC18")
      (value "4011N")
      (footprint "eagle-import:DIL14")
      (libsource (lib "eagle-import") (part "4011N"))
    )
    (comp (ref "IC19")
      (value "4069N")
      (footprint "eagle-import:DIL14")
      (libsource (lib "eagle-import") (part "4069N"))
    )
    (comp (ref "Q1")
      (value "BD140")
      (footprint "eagle-import:TO126")
      (libsource (lib "eagle-import") (part "BD140"))
    )
    (comp (ref "Q2")
      (value "BD140")
      (footprint "eagle-import:TO126")
      (libsource (lib "eagle-import") (part "BD140"))
    )
    (comp (ref "Q3")
      (value "BD140")
      (footprint "eagle-import:TO126")
      (libsource (lib "eagle-import") (part "BD140"))
    )
    (comp (ref "Q4")
      (value "BD140")
      (footprint "eagle-import:TO126")
      (libsource (lib "eagle-import") (part "BD140"))
    )
    (comp (ref "Q5")
      (value "BD140")
      (footprint "eagle-import:TO126")
      (libsource (lib "eagle-import") (part "BD140"))
    )
    (comp (ref "Q6")
      (value "BD140")
      (footprint "eagle-import:TO126")
      (libsource (lib "eagle-import") (part "BD140"))
    )
    (comp (ref "Q7")
      (value "BD140")
      (footprint "eagle-import:TO126")
      (libsource (lib "eagle-import") (part "BD140"))
    )
    (comp (ref "Q8")
      (value "BD140")
      (footprint "eagle-import:TO126")
      (libsource (lib "eagle-import") (part "BD140"))
    )
    (comp (ref "Q9")
      (value "BD140")
      (footprint "eagle-import:TO126")
      (libsource (lib "eagle-import") (part "BD140"))
    )
    (comp (ref "Q10")
      (value "BD140")
      (footprint "eagle-import:TO126")
      (libsource (lib "eagle-import") (part "BD140"))
    )
    (comp (ref "Q11")
      (value "BD140")
      (footprint "eagle-import:TO126")
      (libsource (lib "eagle-import") (part "BD140"))
    )
    (comp (ref "R1")
      (value "10Ohm/2W")
      (footprint "eagle-import:0411_15")
      (libsource (lib "eagle-import") (part "R-EU_0411/15"))
    )
    (comp (ref "R2")
      (value "10Ohm/2W")
      (footprint "eagle-import:0411_15")
      (libsource (lib "eagle-import") (part "R-EU_0411/15"))
    )
    (comp (ref "R3")
      (value "15Ohm/1W")
      (footprint "eagle-import:0309_12")
      (libsource (lib "eagle-import") (part "R-EU_0309/12"))
    )
    (comp (ref "R4")
      (value "15Ohm/1W")
      (footprint "eagle-import:0309_12")
      (libsource (lib "eagle-import") (part "R-EU_0309/12"))
    )
    (comp (ref "R5")
      (value "12K/1W")
      (footprint "eagle-import:0309_12")
      (libsource (lib "eagle-import") (part "R-EU_0309/12"))
    )
    (comp (ref "R6")
      (value "11K")
      (footprint "eagle-import:0309_12")
      (libsource (lib "eagle-import") (part "R-EU_0309/12"))
    )
    (comp (ref "R7")
      (value "2K")
      (footprint "eagle-import:RTRIM3339P")
      (libsource (lib "eagle-import") (part "R-TRIMM3339P"))
    )
    (comp (ref "R8")
      (value "100Ohm/1W")
      (footprint "eagle-import:0411_15")
      (libsource (lib "eagle-import") (part "R-EU_0411/15"))
    )
    (comp (ref "R9")
      (value "2K")
      (footprint "eagle-import:RTRIM3339P")
      (libsource (lib "eagle-import") (part "R-TRIMM3339P"))
    )
    (comp (ref "R10")
      (value "10Ohm/2W")
      (footprint "eagle-import:0411_15")
      (libsource (lib "eagle-import") (part "R-EU_0411/15"))
    )
    (comp (ref "R11")
      (value "3K/1W")
      (footprint "eagle-import:0411_15")
      (libsource (lib "eagle-import") (part "R-EU_0411/15"))
    )
    (comp (ref "R12")
      (value "3K/1W")
      (footprint "eagle-import:0411_15")
      (libsource (lib "eagle-import") (part "R-EU_0411/15"))
    )
    (comp (ref "R13")
      (value "620K/1W")
      (footprint "eagle-import:0411_15")
      (libsource (lib "eagle-import") (part "R-EU_0411/15"))
    )
    (comp (ref "R14")
      (value "6K2/1W")
      (footprint "eagle-import:0411_15")
      (libsource (lib "eagle-import") (part "R-EU_0411/15"))
    )
    (comp (ref "R15")
      (value "30K/1W")
      (footprint "eagle-import:0411_15")
      (libsource (lib "eagle-import") (part "R-EU_0411/15"))
    )
    (comp (ref "R16")
      (value "150K/1W")
      (footprint "eagle-import:0411_15")
      (libsource (lib "eagle-import") (part "R-EU_0411/15"))
    )
    (comp (ref "R17")
      (value "30K/1W")
      (footprint "eagle-import:0411_15")
      (libsource (lib "eagle-import") (part "R-EU_0411/15"))
    )
    (comp (ref "R18")
      (value "6K2/1W")
      (footprint "eagle-import:0411_15")
      (libsource (lib "eagle-import") (part "R-EU_0411/15"))
    )
    (comp (ref "R19")
      (value "2K")
      (footprint "eagle-import:RTRIM3339P")
      (libsource (lib "eagle-import") (part "R-TRIMM3339P"))
    )
    (comp (ref "R20")
      (value "6K2/1W")
      (footprint "eagle-import:0411_15")
      (libsource (lib "eagle-import") (part "R-EU_0411/15"))
    )
    (comp (ref "R21")
      (value "51K/1W")
      (footprint "eagle-import:0411_15")
      (libsource (lib "eagle-import") (part "R-EU_0411/15"))
    )
    (comp (ref "R22")
      (value "12K/1W")
      (footprint "eagle-import:0411_15")
      (libsource (lib "eagle-import") (part "R-EU_0411/15"))
    )
    (comp (ref "R23")
      (value "300K/1W")
      (footprint "eagle-import:0411_15")
      (libsource (lib "eagle-import") (part "R-EU_0411/15"))
    )
    (comp (ref "R24")
      (value "6K2/1W")
      (footprint "eagle-import:0411_15")
      (libsource (lib "eagle-import") (part "R-EU_0411/15"))
    )
    (comp (ref "R25")
      (value "820Ohm/1W")
      (footprint "eagle-import:0411_15")
      (libsource (lib "eagle-import") (part "R-EU_0411/15"))
    )
    (comp (ref "R26")
      (value "820Ohm/1W")
      (footprint "eagle-import:0411_15")
      (libsource (lib "eagle-import") (part "R-EU_0411/15"))
    )
    (comp (ref "R27")
      (value "10K/1W")
      (footprint "eagle-import:0411_15")
      (libsource (lib "eagle-import") (part "R-EU_0411/15"))
    )
    (comp (ref "R28")
      (value "10K/1W")
      (footprint "eagle-import:0411_15")
      (libsource (lib "eagle-import") (part "R-EU_0411/15"))
    )
    (comp (ref "R29")
      (value "2K/1W")
      (footprint "eagle-import:0411_15")
      (libsource (lib "eagle-import") (part "R-EU_0411/15"))
    )
    (comp (ref "R30")
      (value "2K/1W")
      (footprint "eagle-import:0411_15")
      (libsource (lib "eagle-import") (part "R-EU_0411/15"))
    )
    (comp (ref "R31")
      (value "15K/1W")
      (footprint "eagle-import:0411_15")
      (libsource (lib "eagle-import") (part "R-EU_0411/15"))
    )
    (comp (ref "R32")
      (value "15K/1W")
      (footprint "eagle-import:0411_15")
      (libsource (lib "eagle-import") (part "R-EU_0411/15"))
    )
    (comp (ref "R33")
      (value "1K/1W")
      (footprint "eagle-import:0411_15")
      (libsource (lib "eagle-import") (part "R-EU_0411/15"))
    )
    (comp (ref "R34")
      (value "1K/1W")
      (footprint "eagle-import:0411_15")
      (libsource (lib "eagle-import") (part "R-EU_0411/15"))
    )
    (comp (ref "R35")
      (value "6K8/1W")
      (footprint "eagle-import:0411_15")
      (libsource (lib "eagle-import") (part "R-EU_0411/15"))
    )
    (comp (ref "R36")
      (value "6K8/1W")
      (footprint "eagle-import:0411_15")
      (libsource (lib "eagle-import") (part "R-EU_0411/15"))
    )
    (comp (ref "R37")
      (value "51/1W")
      (footprint "eagle-import:0411_15")
      (libsource (lib "eagle-import") (part "R-EU_0411/15"))
    )
    (comp (ref "R38")
      (value "2K7/1W")
      (footprint "eagle-import:0411_15")
      (libsource (lib "eagle-import") (part "R-EU_0411/15"))
    )
    (comp (ref "R39")
      (value "2K7/1W")
      (footprint "eagle-import:0411_15")
      (libsource (lib "eagle-import") (part "R-EU_0411/15"))
    )
    (comp (ref "R40")
      (value "51/1W")
      (footprint "eagle-import:0411_15")
      (libsource (lib "eagle-import") (part "R-EU_0411/15"))
    )
    (comp (ref "R41")
      (value "2K/1W")
      (footprint "eagle-import:0411_15")
      (libsource (lib "eagle-import") (part "R-EU_0411/15"))
    )
    (comp (ref "R42")
      (value "30K/1W")
      (footprint "eagle-import:0411_15")
      (libsource (lib "eagle-import") (part "R-EU_0411/15"))
    )
    (comp (ref "R43")
      (value "51K/1W")
      (footprint "eagle-import:0411_15")
      (libsource (lib "eagle-import") (part "R-EU_0411/15"))
    )
    (comp (ref "R44")
      (value "15K/1W")
      (footprint "eagle-import:0411_15")
      (libsource (lib "eagle-import") (part "R-EU_0411/15"))
    )
    (comp (ref "R45")
      (value "15K/1W")
      (footprint "eagle-import:0411_15")
      (libsource (lib "eagle-import") (part "R-EU_0411/15"))
    )
    (comp (ref "R46")
      (value "560K/1W")
      (footprint "eagle-import:0411_15")
      (libsource (lib "eagle-import") (part "R-EU_0411/15"))
    )
    (comp (ref "R47")
      (value "62K/1W")
      (footprint "eagle-import:0411_15")
      (libsource (lib "eagle-import") (part "R-EU_0411/15"))
    )
    (comp (ref "R48")
      (value "2K")
      (footprint "eagle-import:RTRIM3339P")
      (libsource (lib "eagle-import") (part "R-TRIMM3339P"))
    )
    (comp (ref "R49")
      (value "20K/1W")
      (footprint "eagle-import:0411_15")
      (libsource (lib "eagle-import") (part "R-EU_0411/15"))
    )
    (comp (ref "R50")
      (value "1K5/1W")
      (footprint "eagle-import:0411_15")
      (libsource (lib "eagle-import") (part "R-EU_0411/15"))
    )
    (comp (ref "R51")
      (value "1K2/1W")
      (footprint "eagle-import:0411_15")
      (libsource (lib "eagle-import") (part "R-EU_0411/15"))
    )
    (comp (ref "R52")
      (value "5K1/1W")
      (footprint "eagle-import:0411_15")
      (libsource (lib "eagle-import") (part "R-EU_0411/15"))
    )
    (comp (ref "R53")
      (value "120K/1W")
      (footprint "eagle-import:0411_15")
      (libsource (lib "eagle-import") (part "R-EU_0411/15"))
    )
    (comp (ref "R54")
      (value "30K/1W")
      (footprint "eagle-import:0411_15")
      (libsource (lib "eagle-import") (part "R-EU_0411/15"))
    )
    (comp (ref "R55")
      (value "100K/1W")
      (footprint "eagle-import:0411_15")
      (libsource (lib "eagle-import") (part "R-EU_0411/15"))
    )
    (comp (ref "R56")
      (value "10K/1W")
      (footprint "eagle-import:0411_15")
      (libsource (lib "eagle-import") (part "R-EU_0411/15"))
    )
    (comp (ref "R57")
      (value "100K/1W")
      (footprint "eagle-import:0411_15")
      (libsource (lib "eagle-import") (part "R-EU_0411/15"))
    )
    (comp (ref "R58")
      (value "6K8/1W")
      (footprint "eagle-import:0411_15")
      (libsource (lib "eagle-import") (part "R-EU_0411/15"))
    )
    (comp (ref "R59")
      (value "150K/1W")
      (footprint "eagle-import:0411_15")
      (libsource (lib "eagle-import") (part "R-EU_0411/15"))
    )
    (comp (ref "R60")
      (value "5K1/1W")
      (footprint "eagle-import:0411_15")
      (libsource (lib "eagle-import") (part "R-EU_0411/15"))
    )
    (comp (ref "R61")
      (value "5K1/1W")
      (footprint "eagle-import:0411_15")
      (libsource (lib "eagle-import") (part "R-EU_0411/15"))
    )
    (comp (ref "R62")
      (value "3K/1W")
      (footprint "eagle-import:0411_15")
      (libsource (lib "eagle-import") (part "R-EU_0411/15"))
    )
    (comp (ref "R63")
      (value "10Ohm/2W")
      (footprint "eagle-import:0411_15")
      (libsource (lib "eagle-import") (part "R-EU_0411/15"))
    )
    (comp (ref "R64")
      (value "10Ohm/2W")
      (footprint "eagle-import:0411_15")
      (libsource (lib "eagle-import") (part "R-EU_0411/15"))
    )
    (comp (ref "R65")
      (value "1K/1W")
      (footprint "eagle-import:0411_15")
      (libsource (lib "eagle-import") (part "R-EU_0411/15"))
    )
    (comp (ref "R66")
      (value "120K/1W")
      (footprint "eagle-import:0411_15")
      (libsource (lib "eagle-import") (part "R-EU_0411/15"))
    )
    (comp (ref "R67")
      (value "30K/1W")
      (footprint "eagle-import:0411_15")
      (libsource (lib "eagle-import") (part "R-EU_0411/15"))
    )
    (comp (ref "R68")
      (value "100K/1W")
      (footprint "eagle-import:0411_15")
      (libsource (lib "eagle-import") (part "R-EU_0411/15"))
    )
    (comp (ref "R69")
      (value "10K/1W")
      (footprint "eagle-import:0411_15")
      (libsource (lib "eagle-import") (part "R-EU_0411/15"))
    )
    (comp (ref "R70")
      (value "100K/1W")
      (footprint "eagle-import:0411_15")
      (libsource (lib "eagle-import") (part "R-EU_0411/15"))
    )
    (comp (ref "R71")
      (value "6K8/1W")
      (footprint "eagle-import:0411_15")
      (libsource (lib "eagle-import") (part "R-EU_0411/15"))
    )
    (comp (ref "R72")
      (value "5K1/1W")
      (footprint "eagle-import:0411_15")
      (libsource (lib "eagle-import") (part "R-EU_0411/15"))
    )
    (comp (ref "R73")
      (value "3K/1W")
      (footprint "eagle-import:0411_15")
      (libsource (lib "eagle-import") (part "R-EU_0411/15"))
    )
    (comp (ref "R74")
      (value "10Ohm/2W")
      (footprint "eagle-import:0411_15")
      (libsource (lib "eagle-import") (part "R-EU_0411/15"))
    )
    (comp (ref "R75")
      (value "10Ohm/2W")
      (footprint "eagle-import:0411_15")
      (libsource (lib "eagle-import") (part "R-EU_0411/15"))
    )
    (comp (ref "R76")
      (value "1K/1W")
      (footprint "eagle-import:0411_15")
      (libsource (lib "eagle-import") (part "R-EU_0411/15"))
    )
    (comp (ref "R77")
      (value "2K/1W")
      (footprint "eagle-import:0411_15")
      (libsource (lib "eagle-import") (part "R-EU_0411/15"))
    )
    (comp (ref "R78")
      (value "3K9/1W")
      (footprint "eagle-import:0411_15")
      (libsource (lib "eagle-import") (part "R-EU_0411/15"))
    )
    (comp (ref "R79")
      (value "150K/1W")
      (footprint "eagle-import:0411_15")
      (libsource (lib "eagle-import") (part "R-EU_0411/15"))
    )
    (comp (ref "R80")
      (value "15K/1W")
      (footprint "eagle-import:0411_15")
      (libsource (lib "eagle-import") (part "R-EU_0411/15"))
    )
    (comp (ref "R81")
      (value "2K")
      (footprint "eagle-import:RTRIM3339P")
      (libsource (lib "eagle-import") (part "R-TRIMM3339P"))
    )
    (comp (ref "R82")
      (value "30K/1W")
      (footprint "eagle-import:0411_15")
      (libsource (lib "eagle-import") (part "R-EU_0411/15"))
    )
    (comp (ref "R83")
      (value "30K/1W")
      (footprint "eagle-import:0411_15")
      (libsource (lib "eagle-import") (part "R-EU_0411/15"))
    )
    (comp (ref "R84")
      (value "30K/1W")
      (footprint "eagle-import:0411_15")
      (libsource (lib "eagle-import") (part "R-EU_0411/15"))
    )
    (comp (ref "R85")
      (value "1K/1W")
      (footprint "eagle-import:0411_15")
      (libsource (lib "eagle-import") (part "R-EU_0411/15"))
    )
    (comp (ref "R86")
      (value "5K1/1W")
      (footprint "eagle-import:0411_15")
      (libsource (lib "eagle-import") (part "R-EU_0411/15"))
    )
    (comp (ref "R87")
      (value "15K/1W")
      (footprint "eagle-import:0411_15")
      (libsource (lib "eagle-import") (part "R-EU_0411/15"))
    )
    (comp (ref "R88")
      (value "30K/1W")
      (footprint "eagle-import:0411_15")
      (libsource (lib "eagle-import") (part "R-EU_0411/15"))
    )
    (comp (ref "R89")
      (value "51K/1W")
      (footprint "eagle-import:0411_15")
      (libsource (lib "eagle-import") (part "R-EU_0411/15"))
    )
    (comp (ref "R90")
      (value "15K/1W")
      (footprint "eagle-import:0411_15")
      (libsource (lib "eagle-import") (part "R-EU_0411/15"))
    )
    (comp (ref "R91")
      (value "15K/1W")
      (footprint "eagle-import:0411_15")
      (libsource (lib "eagle-import") (part "R-EU_0411/15"))
    )
    (comp (ref "R92")
      (value "560K/1W")
      (footprint "eagle-import:0411_15")
      (libsource (lib "eagle-import") (part "R-EU_0411/15"))
    )
    (comp (ref "R93")
      (value "62K/1W")
      (footprint "eagle-import:0411_15")
      (libsource (lib "eagle-import") (part "R-EU_0411/15"))
    )
    (comp (ref "R94")
      (value "2K")
      (footprint "eagle-import:RTRIM3339P")
      (libsource (lib "eagle-import") (part "R-TRIMM3339P"))
    )
    (comp (ref "R95")
      (value "20K/1W")
      (footprint "eagle-import:0411_15")
      (libsource (lib "eagle-import") (part "R-EU_0411/15"))
    )
    (comp (ref "R96")
      (value "1K5/1W")
      (footprint "eagle-import:0411_15")
      (libsource (lib "eagle-import") (part "R-EU_0411/15"))
    )
    (comp (ref "R97")
      (value "1K2/1W")
      (footprint "eagle-import:0411_15")
      (libsource (lib "eagle-import") (part "R-EU_0411/15"))
    )
    (comp (ref "R98")
      (value "5K1/1W")
      (footprint "eagle-import:0411_15")
      (libsource (lib "eagle-import") (part "R-EU_0411/15"))
    )
    (comp (ref "R99")
      (value "120K/1W")
      (footprint "eagle-import:0411_15")
      (libsource (lib "eagle-import") (part "R-EU_0411/15"))
    )
    (comp (ref "R100")
      (value "30K/1W")
      (footprint "eagle-import:0411_15")
      (libsource (lib "eagle-import") (part "R-EU_0411/15"))
    )
    (comp (ref "R101")
      (value "100K/1W")
      (footprint "eagle-import:0411_15")
      (libsource (lib "eagle-import") (part "R-EU_0411/15"))
    )
    (comp (ref "R102")
      (value "10K/1W")
      (footprint "eagle-import:0411_15")
      (libsource (lib "eagle-import") (part "R-EU_0411/15"))
    )
    (comp (ref "R103")
      (value "100K/1W")
      (footprint "eagle-import:0411_15")
      (libsource (lib "eagle-import") (part "R-EU_0411/15"))
    )
    (comp (ref "R104")
      (value "6K8/1W")
      (footprint "eagle-import:0411_15")
      (libsource (lib "eagle-import") (part "R-EU_0411/15"))
    )
    (comp (ref "R105")
      (value "150K/1W")
      (footprint "eagle-import:0411_15")
      (libsource (lib "eagle-import") (part "R-EU_0411/15"))
    )
    (comp (ref "R106")
      (value "5K1/1W")
      (footprint "eagle-import:0411_15")
      (libsource (lib "eagle-import") (part "R-EU_0411/15"))
    )
    (comp (ref "R107")
      (value "5K1/1W")
      (footprint "eagle-import:0411_15")
      (libsource (lib "eagle-import") (part "R-EU_0411/15"))
    )
    (comp (ref "R108")
      (value "3K/1W")
      (footprint "eagle-import:0411_15")
      (libsource (lib "eagle-import") (part "R-EU_0411/15"))
    )
    (comp (ref "R109")
      (value "10Ohm/2W")
      (footprint "eagle-import:0411_15")
      (libsource (lib "eagle-import") (part "R-EU_0411/15"))
    )
    (comp (ref "R110")
      (value "10Ohm/2W")
      (footprint "eagle-import:0411_15")
      (libsource (lib "eagle-import") (part "R-EU_0411/15"))
    )
    (comp (ref "R111")
      (value "1K/1W")
      (footprint "eagle-import:0411_15")
      (libsource (lib "eagle-import") (part "R-EU_0411/15"))
    )
    (comp (ref "R112")
      (value "120K/1W")
      (footprint "eagle-import:0411_15")
      (libsource (lib "eagle-import") (part "R-EU_0411/15"))
    )
    (comp (ref "R113")
      (value "30K/1W")
      (footprint "eagle-import:0411_15")
      (libsource (lib "eagle-import") (part "R-EU_0411/15"))
    )
    (comp (ref "R114")
      (value "100K/1W")
      (footprint "eagle-import:0411_15")
      (libsource (lib "eagle-import") (part "R-EU_0411/15"))
    )
    (comp (ref "R115")
      (value "10K/1W")
      (footprint "eagle-import:0411_15")
      (libsource (lib "eagle-import") (part "R-EU_0411/15"))
    )
    (comp (ref "R116")
      (value "100K/1W")
      (footprint "eagle-import:0411_15")
      (libsource (lib "eagle-import") (part "R-EU_0411/15"))
    )
    (comp (ref "R117")
      (value "6K8/1W")
      (footprint "eagle-import:0411_15")
      (libsource (lib "eagle-import") (part "R-EU_0411/15"))
    )
    (comp (ref "R118")
      (value "5K1/1W")
      (footprint "eagle-import:0411_15")
      (libsource (lib "eagle-import") (part "R-EU_0411/15"))
    )
    (comp (ref "R119")
      (value "3K/1W")
      (footprint "eagle-import:0411_15")
      (libsource (lib "eagle-import") (part "R-EU_0411/15"))
    )
    (comp (ref "R120")
      (value "10Ohm/2W")
      (footprint "eagle-import:0411_15")
      (libsource (lib "eagle-import") (part "R-EU_0411/15"))
    )
    (comp (ref "R121")
      (value "10Ohm/2W")
      (footprint "eagle-import:0411_15")
      (libsource (lib "eagle-import") (part "R-EU_0411/15"))
    )
    (comp (ref "R122")
      (value "1K/1W")
      (footprint "eagle-import:0411_15")
      (libsource (lib "eagle-import") (part "R-EU_0411/15"))
    )
    (comp (ref "R123")
      (value "2K/1W")
      (footprint "eagle-import:0411_15")
      (libsource (lib "eagle-import") (part "R-EU_0411/15"))
    )
    (comp (ref "R124")
      (value "3K9/1W")
      (footprint "eagle-import:0411_15")
      (libsource (lib "eagle-import") (part "R-EU_0411/15"))
    )
    (comp (ref "R125")
      (value "15K/1W")
      (footprint "eagle-import:0411_15")
      (libsource (lib "eagle-import") (part "R-EU_0411/15"))
    )
    (comp (ref "R126")
      (value "2K")
      (footprint "eagle-import:RTRIM3339P")
      (libsource (lib "eagle-import") (part "R-TRIMM3339P"))
    )
    (comp (ref "R127")
      (value "150K/1W")
      (footprint "eagle-import:0411_15")
      (libsource (lib "eagle-import") (part "R-EU_0411/15"))
    )
    (comp (ref "R128")
      (value "30K/1W")
      (footprint "eagle-import:0411_15")
      (libsource (lib "eagle-import") (part "R-EU_0411/15"))
    )
    (comp (ref "R129")
      (value "30K/1W")
      (footprint "eagle-import:0411_15")
      (libsource (lib "eagle-import") (part "R-EU_0411/15"))
    )
    (comp (ref "R130")
      (value "30K/1W")
      (footprint "eagle-import:0411_15")
      (libsource (lib "eagle-import") (part "R-EU_0411/15"))
    )
    (comp (ref "R131")
      (value "1K/1W")
      (footprint "eagle-import:0411_15")
      (libsource (lib "eagle-import") (part "R-EU_0411/15"))
    )
    (comp (ref "R132")
      (value "5K1/1W")
      (footprint "eagle-import:0411_15")
      (libsource (lib "eagle-import") (part "R-EU_0411/15"))
    )
    (comp (ref "R133")
      (value "30K/1W")
      (footprint "eagle-import:0411_15")
      (libsource (lib "eagle-import") (part "R-EU_0411/15"))
    )
    (comp (ref "R134")
      (value "30K/1W")
      (footprint "eagle-import:0411_15")
      (libsource (lib "eagle-import") (part "R-EU_0411/15"))
    )
    (comp (ref "R135")
      (value "2K")
      (footprint "eagle-import:RTRIM3339P")
      (libsource (lib "eagle-import") (part "R-TRIMM3339P"))
    )
    (comp (ref "R136")
      (value "7K5/1W")
      (footprint "eagle-import:0411_15")
      (libsource (lib "eagle-import") (part "R-EU_0411/15"))
    )
    (comp (ref "R137")
      (value "1K5/1W")
      (footprint "eagle-import:0411_15")
      (libsource (lib "eagle-import") (part "R-EU_0411/15"))
    )
    (comp (ref "R138")
      (value "5K1/1W")
      (footprint "eagle-import:0411_15")
      (libsource (lib "eagle-import") (part "R-EU_0411/15"))
    )
    (comp (ref "R139")
      (value "680Ohm/1W")
      (footprint "eagle-import:0411_15")
      (libsource (lib "eagle-import") (part "R-EU_0411/15"))
    )
    (comp (ref "R140")
      (value "2K")
      (footprint "eagle-import:RTRIM3339P")
      (libsource (lib "eagle-import") (part "R-TRIMM3339P"))
    )
    (comp (ref "R141")
      (value "7K5/1W")
      (footprint "eagle-import:0411_15")
      (libsource (lib "eagle-import") (part "R-EU_0411/15"))
    )
    (comp (ref "R142")
      (value "1K5/1W")
      (footprint "eagle-import:0411_15")
      (libsource (lib "eagle-import") (part "R-EU_0411/15"))
    )
    (comp (ref "R143")
      (value "5K1/1W")
      (footprint "eagle-import:0411_15")
      (libsource (lib "eagle-import") (part "R-EU_0411/15"))
    )
    (comp (ref "R144")
      (value "680Ohm/1W")
      (footprint "eagle-import:0411_15")
      (libsource (lib "eagle-import") (part "R-EU_0411/15"))
    )
    (comp (ref "R145")
      (value "2K")
      (footprint "eagle-import:RTRIM3339P")
      (libsource (lib "eagle-import") (part "R-TRIMM3339P"))
    )
    (comp (ref "R146")
      (value "30K/1W")
      (footprint "eagle-import:0411_15")
      (libsource (lib "eagle-import") (part "R-EU_0411/15"))
    )
    (comp (ref "R147")
      (value "62K/1W")
      (footprint "eagle-import:0411_15")
      (libsource (lib "eagle-import") (part "R-EU_0411/15"))
    )
    (comp (ref "R148")
      (value "200Ohm/1W")
      (footprint "eagle-import:0411_15")
      (libsource (lib "eagle-import") (part "R-EU_0411/15"))
    )
    (comp (ref "R149")
      (value "30K/1W")
      (footprint "eagle-import:0411_15")
      (libsource (lib "eagle-import") (part "R-EU_0411/15"))
    )
    (comp (ref "R150")
      (value "30K/1W")
      (footprint "eagle-import:0411_15")
      (libsource (lib "eagle-import") (part "R-EU_0411/15"))
    )
    (comp (ref "R151")
      (value "30K/1W")
      (footprint "eagle-import:0411_15")
      (libsource (lib "eagle-import") (part "R-EU_0411/15"))
    )
    (comp (ref "R152")
      (value "100K/1W")
      (footprint "eagle-import:0411_15")
      (libsource (lib "eagle-import") (part "R-EU_0411/15"))
    )
    (comp (ref "R153")
      (value "51K/1W")
      (footprint "eagle-import:0411_15")
      (libsource (lib "eagle-import") (part "R-EU_0411/15"))
    )
    (comp (ref "R154")
      (value "12K/1W")
      (footprint "eagle-import:0411_15")
      (libsource (lib "eagle-import") (part "R-EU_0411/15"))
    )
    (comp (ref "R155")
      (value "100K/1W")
      (footprint "eagle-import:0411_15")
      (libsource (lib "eagle-import") (part "R-EU_0411/15"))
    )
    (comp (ref "R156")
      (value "12K/1W")
      (footprint "eagle-import:0411_15")
      (libsource (lib "eagle-import") (part "R-EU_0411/15"))
    )
    (comp (ref "R157")
      (value "300K/1W")
      (footprint "eagle-import:0411_15")
      (libsource (lib "eagle-import") (part "R-EU_0411/15"))
    )
    (comp (ref "R158")
      (value "12K/1W")
      (footprint "eagle-import:0411_15")
      (libsource (lib "eagle-import") (part "R-EU_0411/15"))
    )
    (comp (ref "R159")
      (value "200K/1W")
      (footprint "eagle-import:0411_15")
      (libsource (lib "eagle-import") (part "R-EU_0411/15"))
    )
    (comp (ref "R160")
      (value "2K")
      (footprint "eagle-import:RTRIM3339P")
      (libsource (lib "eagle-import") (part "R-TRIMM3339P"))
    )
    (comp (ref "R161")
      (value "30K/1W")
      (footprint "eagle-import:0411_15")
      (libsource (lib "eagle-import") (part "R-EU_0411/15"))
    )
    (comp (ref "R162")
      (value "62K/1W")
      (footprint "eagle-import:0411_15")
      (libsource (lib "eagle-import") (part "R-EU_0411/15"))
    )
    (comp (ref "R163")
      (value "200Ohm/1W")
      (footprint "eagle-import:0411_15")
      (libsource (lib "eagle-import") (part "R-EU_0411/15"))
    )
    (comp (ref "R164")
      (value "30K/1W")
      (footprint "eagle-import:0411_15")
      (libsource (lib "eagle-import") (part "R-EU_0411/15"))
    )
    (comp (ref "R165")
      (value "30K/1W")
      (footprint "eagle-import:0411_15")
      (libsource (lib "eagle-import") (part "R-EU_0411/15"))
    )
    (comp (ref "R166")
      (value "30K/1W")
      (footprint "eagle-import:0411_15")
      (libsource (lib "eagle-import") (part "R-EU_0411/15"))
    )
    (comp (ref "R167")
      (value "100K/1W")
      (footprint "eagle-import:0411_15")
      (libsource (lib "eagle-import") (part "R-EU_0411/15"))
    )
    (comp (ref "R168")
      (value "51K/1W")
      (footprint "eagle-import:0411_15")
      (libsource (lib "eagle-import") (part "R-EU_0411/15"))
    )
    (comp (ref "R169")
      (value "12K/1W")
      (footprint "eagle-import:0411_15")
      (libsource (lib "eagle-import") (part "R-EU_0411/15"))
    )
    (comp (ref "R170")
      (value "100K/1W")
      (footprint "eagle-import:0411_15")
      (libsource (lib "eagle-import") (part "R-EU_0411/15"))
    )
    (comp (ref "R171")
      (value "12K/1W")
      (footprint "eagle-import:0411_15")
      (libsource (lib "eagle-import") (part "R-EU_0411/15"))
    )
    (comp (ref "R172")
      (value "300K/1W")
      (footprint "eagle-import:0411_15")
      (libsource (lib "eagle-import") (part "R-EU_0411/15"))
    )
    (comp (ref "R173")
      (value "12K/1W")
      (footprint "eagle-import:0411_15")
      (libsource (lib "eagle-import") (part "R-EU_0411/15"))
    )
    (comp (ref "R174")
      (value "200K/1W")
      (footprint "eagle-import:0411_15")
      (libsource (lib "eagle-import") (part "R-EU_0411/15"))
    )
    (comp (ref "R175")
      (value "12K/1W")
      (footprint "eagle-import:0411_15")
      (libsource (lib "eagle-import") (part "R-EU_0411/15"))
    )
    (comp (ref "R176")
      (value "200K/1W")
      (footprint "eagle-import:0411_15")
      (libsource (lib "eagle-import") (part "R-EU_0411/15"))
    )
    (comp (ref "R177")
      (value "12K/1W")
      (footprint "eagle-import:0411_15")
      (libsource (lib "eagle-import") (part "R-EU_0411/15"))
    )
    (comp (ref "T1")
      (value "BD139")
      (footprint "eagle-import:TO126")
      (libsource (lib "eagle-import") (part "BD139"))
    )
    (comp (ref "T2")
      (value "BD139")
      (footprint "eagle-import:TO126")
      (libsource (lib "eagle-import") (part "BD139"))
    )
    (comp (ref "T3")
      (value "BD139")
      (footprint "eagle-import:TO126")
      (libsource (lib "eagle-import") (part "BD139"))
    )
    (comp (ref "T4")
      (value "BD139")
      (footprint "eagle-import:TO126")
      (libsource (lib "eagle-import") (part "BD139"))
    )
    (comp (ref "T5")
      (value "BD139")
      (footprint "eagle-import:TO126")
      (libsource (lib "eagle-import") (part "BD139"))
    )
    (comp (ref "T6")
      (value "BD139")
      (footprint "eagle-import:TO126")
      (libsource (lib "eagle-import") (part "BD139"))
    )
    (comp (ref "T7")
      (value "BD139")
      (footprint "eagle-import:TO126")
      (libsource (lib "eagle-import") (part "BD139"))
    )
    (comp (ref "T8")
      (value "BD139")
      (footprint "eagle-import:TO126")
      (libsource (lib "eagle-import") (part "BD139"))
    )
    (comp (ref "T9")
      (value "BD139")
      (footprint "eagle-import:TO126")
      (libsource (lib "eagle-import") (part "BD139"))
    )
    (comp (ref "T10")
      (value "BD139")
      (footprint "eagle-import:TO126")
      (libsource (lib "eagle-import") (part "BD139"))
    )
    (comp (ref "T11")
      (value "BD139")
      (footprint "eagle-import:TO126")
      (libsource (lib "eagle-import") (part "BD139"))
    )
    (comp (ref "T12")
      (value "BT148")
      (footprint "eagle-import:SOT82S")
      (libsource (lib "eagle-import") (part "BT148"))
    )
    (comp (ref "T13")
      (value "BT148")
      (footprint "eagle-import:SOT82S")
      (libsource (lib "eagle-import") (part "BT148"))
    )
    (comp (ref "T14")
      (value "BT148")
      (footprint "eagle-import:SOT82S")
      (libsource (lib "eagle-import") (part "BT148"))
    )
    (comp (ref "T15")
      (value "BT148")
      (footprint "eagle-import:SOT82S")
      (libsource (lib "eagle-import") (part "BT148"))
    )
    (comp (ref "TR1")
      (value "CTX02-14659")
      (footprint "eagle-import:CTX02-14659")
      (libsource (lib "eagle-import") (part "CTX02-14659"))
    )
    (comp (ref "TR2")
      (value "CTX02-14659")
      (footprint "eagle-import:CTX02-14659")
      (libsource (lib "eagle-import") (part "CTX02-14659"))
    )
    (comp (ref "TR3")
      (value "EI54-2")
      (footprint "eagle-import:EI54-2")
      (libsource (lib "eagle-import") (part "EI54-2"))
    )
    (comp (ref "TR4")
      (value "EI54-2")
      (footprint "eagle-import:EI54-2")
      (libsource (lib "eagle-import") (part "EI54-2"))
    )
    (comp (ref "TR5")
      (value "EI54-2")
      (footprint "eagle-import:EI54-2")
      (libsource (lib "eagle-import") (part "EI54-2"))
    )
    (comp (ref "TR6")
      (value "EI54-2")
      (footprint "eagle-import:EI54-2")
      (libsource (lib "eagle-import") (part "EI54-2"))
    )
  )
  (nets
    (net (code "1") (name "+12V") (class "Default")
      (node (ref "C12") (pin "1") (pinfunction "1_1") (pintype "passive"))
      (node (ref "C13") (pin "1") (pinfunction "1_1") (pintype "passive"))
      (node (ref "C16") (pin "1") (pinfunction "1_1") (pintype "passive"))
      (node (ref "C17") (pin "1") (pinfunction "1_1") (pintype "passive"))
      (node (ref "C20") (pin "1") (pinfunction "1_1") (pintype "passive"))
      (node (ref "C21") (pin "1") (pinfunction "1_1") (pintype "passive"))
      (node (ref "C24") (pin "1") (pinfunction "1_1") (pintype "passive"))
      (node (ref "C25") (pin "1") (pinfunction "1_1") (pintype "passive"))
      (node (ref "C28") (pin "1") (pinfunction "1_1") (pintype "passive"))
      (node (ref "C29") (pin "1") (pinfunction "1_1") (pintype "passive"))
      (node (ref "C3") (pin "+") (pinfunction "+_+") (pintype "passive"))
      (node (ref "C32") (pin "1") (pinfunction "1_1") (pintype "passive"))
      (node (ref "C33") (pin "1") (pinfunction "1_1") (pintype "passive"))
      (node (ref "C34") (pin "1") (pinfunction "1_1") (pintype "passive"))
      (node (ref "C5") (pin "1") (pinfunction "1_1") (pintype "passive"))
      (node (ref "C8") (pin "1") (pinfunction "1_1") (pintype "passive"))
      (node (ref "C9") (pin "1") (pinfunction "1_1") (pintype "passive"))
      (node (ref "IC10") (pin "7") (pinfunction "V+_7") (pintype "power_in"))
      (node (ref "IC11") (pin "7") (pinfunction "V+_7") (pintype "power_in"))
      (node (ref "IC12") (pin "7") (pinfunction "V+_7") (pintype "power_in"))
      (node (ref "IC13") (pin "7") (pinfunction "V+_7") (pintype "power_in"))
      (node (ref "IC14") (pin "7") (pinfunction "V+_7") (pintype "power_in"))
      (node (ref "IC15") (pin "12") (pinfunction "I0_12") (pintype "input"))
      (node (ref "IC17") (pin "7") (pinfunction "V+_7") (pintype "power_in"))
      (node (ref "IC3") (pin "7") (pinfunction "V+_7") (pintype "power_in"))
      (node (ref "IC4") (pin "7") (pinfunction "V+_7") (pintype "power_in"))
      (node (ref "IC5") (pin "7") (pinfunction "V+_7") (pintype "power_in"))
      (node (ref "IC6") (pin "7") (pinfunction "V+_7") (pintype "power_in"))
      (node (ref "IC7") (pin "7") (pinfunction "V+_7") (pintype "power_in"))
      (node (ref "IC8") (pin "7") (pinfunction "V+_7") (pintype "power_in"))
      (node (ref "IC9") (pin "7") (pinfunction "V+_7") (pintype "power_in"))
      (node (ref "R103") (pin "2") (pinfunction "2_2") (pintype "passive"))
      (node (ref "R116") (pin "2") (pinfunction "2_2") (pintype "passive"))
      (node (ref "R123") (pin "2") (pinfunction "2_2") (pintype "passive"))
      (node (ref "R146") (pin "2") (pinfunction "2_2") (pintype "passive"))
      (node (ref "R161") (pin "2") (pinfunction "2_2") (pintype "passive"))
      (node (ref "R177") (pin "2") (pinfunction "2_2") (pintype "passive"))
      (node (ref "R3") (pin "2") (pinfunction "2_2") (pintype "passive"))
      (node (ref "R50") (pin "2") (pinfunction "2_2") (pintype "passive"))
      (node (ref "R51") (pin "2") (pinfunction "2_2") (pintype "passive"))
      (node (ref "R57") (pin "2") (pinfunction "2_2") (pintype "passive"))
      (node (ref "R70") (pin "2") (pinfunction "2_2") (pintype "passive"))
      (node (ref "R77") (pin "2") (pinfunction "2_2") (pintype "passive"))
      (node (ref "R96") (pin "2") (pinfunction "2_2") (pintype "passive"))
      (node (ref "R97") (pin "2") (pinfunction "2_2") (pintype "passive"))
    )
    (net (code "2") (name "-12V") (class "Default")
      (node (ref "C10") (pin "2") (pinfunction "2_2") (pintype "passive"))
      (node (ref "C11") (pin "2") (pinfunction "2_2") (pintype "passive"))
      (node (ref "C14") (pin "2") (pinfunction "2_2") (pintype "passive"))
      (node (ref "C15") (pin "2") (pinfunction "2_2") (pintype "passive"))
      (node (ref "C18") (pin "2") (pinfunction "2_2") (pintype "passive"))
      (node (ref "C19") (pin "2") (pinfunction "2_2") (pintype "passive"))
      (node (ref "C22") (pin "2") (pinfunction "2_2") (pintype "passive"))
      (node (ref "C23") (pin "2") (pinfunction "2_2") (pintype "passive"))
      (node (ref "C26") (pin "2") (pinfunction "2_2") (pintype "passive"))
      (node (ref "C27") (pin "2") (pinfunction "2_2") (pintype "passive"))
      (node (ref "C30") (pin "2") (pinfunction "2_2") (pintype "passive"))
      (node (ref "C39") (pin "-") (pinfunction "-_-") (pintype "passive"))
      (node (ref "C4") (pin "-") (pinfunction "-_-") (pintype "passive"))
      (node (ref "C56") (pin "2") (pinfunction "2_2") (pintype "passive"))
      (node (ref "C6") (pin "2") (pinfunction "2_2") (pintype "passive"))
      (node (ref "C64") (pin "2") (pinfunction "2_2") (pintype "passive"))
      (node (ref "C7") (pin "2") (pinfunction "2_2") (pintype "passive"))
      (node (ref "C73") (pin "2") (pinfunction "2_2") (pintype "passive"))
      (node (ref "IC13") (pin "4") (pinfunction "V-_4") (pintype "power_in"))
      (node (ref "IC14") (pin "4") (pinfunction "V-_4") (pintype "power_in"))
      (node (ref "IC17") (pin "4") (pinfunction "V-_4") (pintype "power_in"))
      (node (ref "IC3") (pin "4") (pinfunction "V-_4") (pintype "power_in"))
      (node (ref "IC4") (pin "4") (pinfunction "V-_4") (pintype "power_in"))
      (node (ref "IC5") (pin "4") (pinfunction "V-_4") (pintype "power_in"))
      (node (ref "IC6") (pin "4") (pinfunction "V-_4") (pintype "power_in"))
      (node (ref "IC9") (pin "4") (pinfunction "V-_4") (pintype "power_in"))
      (node (ref "R137") (pin "1") (pinfunction "1_1") (pintype "passive"))
      (node (ref "R139") (pin "1") (pinfunction "1_1") (pintype "passive"))
      (node (ref "R142") (pin "1") (pinfunction "1_1") (pintype "passive"))
      (node (ref "R144") (pin "1") (pinfunction "1_1") (pintype "passive"))
      (node (ref "R20") (pin "1") (pinfunction "1_1") (pintype "passive"))
      (node (ref "R29") (pin "1") (pinfunction "1_1") (pintype "passive"))
      (node (ref "R30") (pin "1") (pinfunction "1_1") (pintype "passive"))
      (node (ref "R31") (pin "1") (pinfunction "1_1") (pintype "passive"))
      (node (ref "R32") (pin "1") (pinfunction "1_1") (pintype "passive"))
      (node (ref "R37") (pin "1") (pinfunction "1_1") (pintype "passive"))
      (node (ref "R38") (pin "1") (pinfunction "1_1") (pintype "passive"))
      (node (ref "R39") (pin "1") (pinfunction "1_1") (pintype "passive"))
      (node (ref "R4") (pin "2") (pinfunction "2_2") (pintype "passive"))
      (node (ref "R40") (pin "1") (pinfunction "1_1") (pintype "passive"))
      (node (ref "R46") (pin "1") (pinfunction "1_1") (pintype "passive"))
      (node (ref "R92") (pin "1") (pinfunction "1_1") (pintype "passive"))
    )
    (net (code "3") (name "/V-") (class "Default")
      (node (ref "IC10") (pin "4") (pinfunction "V-_4") (pintype "power_in"))
    )
    (net (code "4") (name "0V") (class "Default")
      (node (ref "C1") (pin "-") (pinfunction "-_-") (pintype "passive"))
      (node (ref "C10") (pin "1") (pinfunction "1_1") (pintype "passive"))
      (node (ref "C11") (pin "1") (pinfunction "1_1") (pintype "passive"))
      (node (ref "C12") (pin "2") (pinfunction "2_2") (pintype "passive"))
      (node (ref "C13") (pin "2") (pinfunction "2_2") (pintype "passive"))
      (node (ref "C14") (pin "1") (pinfunction "1_1") (pintype "passive"))
      (node (ref "C15") (pin "1") (pinfunction "1_1") (pintype "passive"))
      (node (ref "C16") (pin "2") (pinfunction "2_2") (pintype "passive"))
      (node (ref "C17") (pin "2") (pinfunction "2_2") (pintype "passive"))
      (node (ref "C18") (pin "1") (pinfunction "1_1") (pintype "passive"))
      (node (ref "C19") (pin "1") (pinfunction "1_1") (pintype "passive"))
      (node (ref "C2") (pin "+") (pinfunction "+_+") (pintype "passive"))
      (node (ref "C20") (pin "2") (pinfunction "2_2") (pintype "passive"))
      (node (ref "C21") (pin "2") (pinfunction "2_2") (pintype "passive"))
      (node (ref "C22") (pin "1") (pinfunction "1_1") (pintype "passive"))
      (node (ref "C23") (pin "1") (pinfunction "1_1") (pintype "passive"))
      (node (ref "C24") (pin "2") (pinfunction "2_2") (pintype "passive"))
      (node (ref "C25") (pin "2") (pinfunction "2_2") (pintype "passive"))
      (node (ref "C26") (pin "1") (pinfunction "1_1") (pintype "passive"))
      (node (ref "C27") (pin "1") (pinfunction "1_1") (pintype "passive"))
      (node (ref "C28") (pin "2") (pinfunction "2_2") (pintype "passive"))
      (node (ref "C29") (pin "2") (pinfunction "2_2") (pintype "passive"))
      (node (ref "C3") (pin "-") (pinfunction "-_-") (pintype "passive"))
      (node (ref "C30") (pin "1") (pinfunction "1_1") (pintype "passive"))
      (node (ref "C32") (pin "2") (pinfunction "2_2") (pintype "passive"))
      (node (ref "C33") (pin "2") (pinfunction "2_2") (pintype "passive"))
      (node (ref "C34") (pin "2") (pinfunction "2_2") (pintype "passive"))
      (node (ref "C36") (pin "2") (pinfunction "2_2") (pintype "passive"))
      (node (ref "C37") (pin "2") (pinfunction "2_2") (pintype "passive"))
      (node (ref "C38") (pin "2") (pinfunction "2_2") (pintype "passive"))
      (node (ref "C4") (pin "+") (pinfunction "+_+") (pintype "passive"))
      (node (ref "C5") (pin "2") (pinfunction "2_2") (pintype "passive"))
      (node (ref "C53") (pin "2") (pinfunction "2_2") (pintype "passive"))
      (node (ref "C57") (pin "2") (pinfunction "2_2") (pintype "passive"))
      (node (ref "C58") (pin "2") (pinfunction "2_2") (pintype "passive"))
      (node (ref "C6") (pin "1") (pinfunction "1_1") (pintype "passive"))
      (node (ref "C61") (pin "2") (pinfunction "2_2") (pintype "passive"))
      (node (ref "C65") (pin "2") (pinfunction "2_2") (pintype "passive"))
      (node (ref "C66") (pin "2") (pinfunction "2_2") (pintype "passive"))
      (node (ref "C67") (pin "2") (pinfunction "2_2") (pintype "passive"))
      (node (ref "C68") (pin "2") (pinfunction "2_2") (pintype "passive"))
      (node (ref "C69") (pin "2") (pinfunction "2_2") (pintype "passive"))
      (node (ref "C7") (pin "1") (pinfunction "1_1") (pintype "passive"))
      (node (ref "C70") (pin "2") (pinfunction "2_2") (pintype "passive"))
      (node (ref "C72") (pin "2") (pinfunction "2_2") (pintype "passive"))
      (node (ref "C8") (pin "2") (pinfunction "2_2") (pintype "passive"))
      (node (ref "C9") (pin "2") (pinfunction "2_2") (pintype "passive"))
      (node (ref "D34") (pin "A") (pinfunction "A_A") (pintype "passive"))
      (node (ref "D36") (pin "A") (pinfunction "A_A") (pintype "passive"))
      (node (ref "D47") (pin "A") (pinfunction "A_A") (pintype "passive"))
      (node (ref "D5") (pin "C") (pinfunction "C_C") (pintype "passive"))
      (node (ref "D51") (pin "A") (pinfunction "A_A") (pintype "passive"))
      (node (ref "D53") (pin "A") (pinfunction "A_A") (pintype "passive"))
      (node (ref "D6") (pin "A") (pinfunction "A_A") (pintype "passive"))
      (node (ref "IC10") (pin "3") (pinfunction "+IN_3") (pintype "input"))
      (node (ref "IC11") (pin "3") (pinfunction "+IN_3") (pintype "input"))
      (node (ref "IC7") (pin "3") (pinfunction "+IN_3") (pintype "input"))
      (node (ref "IC9") (pin "3") (pinfunction "+IN_3") (pintype "input"))
      (node (ref "Q7") (pin "2") (pinfunction "C_2") (pintype "passive"))
      (node (ref "Q9") (pin "2") (pinfunction "C_2") (pintype "passive"))
      (node (ref "R104") (pin "1") (pinfunction "1_1") (pintype "passive"))
      (node (ref "R106") (pin "1") (pinfunction "1_1") (pintype "passive"))
      (node (ref "R111") (pin "1") (pinfunction "1_1") (pintype "passive"))
      (node (ref "R117") (pin "1") (pinfunction "1_1") (pintype "passive"))
      (node (ref "R122") (pin "1") (pinfunction "1_1") (pintype "passive"))
      (node (ref "R124") (pin "1") (pinfunction "1_1") (pintype "passive"))
      (node (ref "R128") (pin "2") (pinfunction "2_2") (pintype "passive"))
      (node (ref "R131") (pin "2") (pinfunction "2_2") (pintype "passive"))
      (node (ref "R135") (pin "3") (pinfunction "E_3") (pintype "passive"))
      (node (ref "R138") (pin "2") (pinfunction "2_2") (pintype "passive"))
      (node (ref "R14") (pin "1") (pinfunction "1_1") (pintype "passive"))
      (node (ref "R148") (pin "2") (pinfunction "2_2") (pintype "passive"))
      (node (ref "R151") (pin "2") (pinfunction "2_2") (pintype "passive"))
      (node (ref "R152") (pin "2") (pinfunction "2_2") (pintype "passive"))
      (node (ref "R163") (pin "2") (pinfunction "2_2") (pintype "passive"))
      (node (ref "R166") (pin "2") (pinfunction "2_2") (pintype "passive"))
      (node (ref "R167") (pin "2") (pinfunction "2_2") (pintype "passive"))
      (node (ref "R17") (pin "1") (pinfunction "1_1") (pintype "passive"))
      (node (ref "R176") (pin "1") (pinfunction "1_1") (pintype "passive"))
      (node (ref "R18") (pin "2") (pinfunction "2_2") (pintype "passive"))
      (node (ref "R23") (pin "1") (pinfunction "1_1") (pintype "passive"))
      (node (ref "R24") (pin "2") (pinfunction "2_2") (pintype "passive"))
      (node (ref "R71") (pin "1") (pinfunction "1_1") (pintype "passive"))
      (node (ref "R76") (pin "1") (pinfunction "1_1") (pintype "passive"))
      (node (ref "R78") (pin "1") (pinfunction "1_1") (pintype "passive"))
      (node (ref "R82") (pin "2") (pinfunction "2_2") (pintype "passive"))
      (node (ref "R85") (pin "2") (pinfunction "2_2") (pintype "passive"))
      (node (ref "R87") (pin "1") (pinfunction "1_1") (pintype "passive"))
      (node (ref "R94") (pin "1") (pinfunction "A_1") (pintype "passive"))
      (node (ref "R98") (pin "1") (pinfunction "1_1") (pintype "passive"))
      (node (ref "T13") (pin "C") (pinfunction "C_C") (pintype "passive"))
      (node (ref "T14") (pin "C") (pinfunction "C_C") (pintype "passive"))
      (node (ref "T15") (pin "C") (pinfunction "C_C") (pintype "passive"))
      (node (ref "TR1") (pin "6") (pinfunction "4_6") (pintype "passive"))
      (node (ref "TR2") (pin "6") (pinfunction "4_6") (pintype "passive"))
    )
    (net (code "5") (name "0V1") (class "Default")
      (node (ref "C48") (pin "2") (pinfunction "2_2") (pintype "passive"))
      (node (ref "C49") (pin "2") (pinfunction "2_2") (pintype "passive"))
      (node (ref "C50") (pin "2") (pinfunction "2_2") (pintype "passive"))
      (node (ref "D30") (pin "A") (pinfunction "A_A") (pintype "passive"))
      (node (ref "IC5") (pin "3") (pinfunction "+IN_3") (pintype "input"))
      (node (ref "IC6") (pin "3") (pinfunction "+IN_3") (pintype "input"))
      (node (ref "R140") (pin "3") (pinfunction "E_3") (pintype "passive"))
      (node (ref "R143") (pin "2") (pinfunction "2_2") (pintype "passive"))
      (node (ref "R48") (pin "1") (pinfunction "A_1") (pintype "passive"))
      (node (ref "R52") (pin "1") (pinfunction "1_1") (pintype "passive"))
      (node (ref "R58") (pin "1") (pinfunction "1_1") (pintype "passive"))
      (node (ref "R60") (pin "1") (pinfunction "1_1") (pintype "passive"))
      (node (ref "R65") (pin "1") (pinfunction "1_1") (pintype "passive"))
      (node (ref "T12") (pin "C") (pinfunction "C_C") (pintype "passive"))
    )
    (net (code "6") (name "1CN(1)") (class "Default")
      (node (ref "R41") (pin "1") (pinfunction "1_1") (pintype "passive"))
    )
    (net (code "7") (name "4CN(1)") (class "Default")
      (node (ref "C52") (pin "2") (pinfunction "2_2") (pintype "passive"))
      (node (ref "C55") (pin "2") (pinfunction "2_2") (pintype "passive"))
      (node (ref "C60") (pin "2") (pinfunction "2_2") (pintype "passive"))
      (node (ref "C63") (pin "2") (pinfunction "2_2") (pintype "passive"))
      (node (ref "TR3") (pin "8") (pinfunction "3_8") (pintype "passive"))
      (node (ref "TR4") (pin "8") (pinfunction "3_8") (pintype "passive"))
      (node (ref "TR5") (pin "8") (pinfunction "3_8") (pintype "passive"))
      (node (ref "TR6") (pin "8") (pinfunction "3_8") (pintype "passive"))
    )
    (net (code "8") (name "4CN(2)") (class "Default")
      (node (ref "C52") (pin "1") (pinfunction "1_1") (pintype "passive"))
      (node (ref "C55") (pin "1") (pinfunction "1_1") (pintype "passive"))
      (node (ref "C60") (pin "1") (pinfunction "1_1") (pintype "passive"))
      (node (ref "C63") (pin "1") (pinfunction "1_1") (pintype "passive"))
      (node (ref "TR3") (pin "9") (pinfunction "4_9") (pintype "passive"))
      (node (ref "TR4") (pin "9") (pinfunction "4_9") (pintype "passive"))
      (node (ref "TR5") (pin "9") (pinfunction "4_9") (pintype "passive"))
      (node (ref "TR6") (pin "9") (pinfunction "4_9") (pintype "passive"))
    )
    (net (code "9") (name "4CN(3)") (class "Default")
      (node (ref "C51") (pin "2") (pinfunction "2_2") (pintype "passive"))
      (node (ref "C54") (pin "2") (pinfunction "2_2") (pintype "passive"))
      (node (ref "C59") (pin "2") (pinfunction "2_2") (pintype "passive"))
      (node (ref "C62") (pin "2") (pinfunction "2_2") (pintype "passive"))
      (node (ref "TR3") (pin "13") (pinfunction "5_13") (pintype "passive"))
      (node (ref "TR4") (pin "13") (pinfunction "5_13") (pintype "passive"))
      (node (ref "TR5") (pin "13") (pinfunction "5_13") (pintype "passive"))
      (node (ref "TR6") (pin "13") (pinfunction "5_13") (pintype "passive"))
    )
    (net (code "10") (name "4CN(4)") (class "Default")
      (node (ref "C51") (pin "1") (pinfunction "1_1") (pintype "passive"))
      (node (ref "C54") (pin "1") (pinfunction "1_1") (pintype "passive"))
      (node (ref "C59") (pin "1") (pinfunction "1_1") (pintype "passive"))
      (node (ref "C62") (pin "1") (pinfunction "1_1") (pintype "passive"))
      (node (ref "TR3") (pin "14") (pinfunction "6_14") (pintype "passive"))
      (node (ref "TR4") (pin "14") (pinfunction "6_14") (pintype "passive"))
      (node (ref "TR5") (pin "14") (pinfunction "6_14") (pintype "passive"))
      (node (ref "TR6") (pin "14") (pinfunction "6_14") (pintype "passive"))
    )
    (net (code "11") (name "A") (class "Default")
      (node (ref "C36") (pin "1") (pinfunction "1_1") (pintype "passive"))
      (node (ref "R11") (pin "1") (pinfunction "1_1") (pintype "passive"))
      (node (ref "R42") (pin "1") (pinfunction "1_1") (pintype "passive"))
      (node (ref "R8") (pin "2") (pinfunction "2_2") (pintype "passive"))
      (node (ref "R88") (pin "1") (pinfunction "1_1") (pintype "passive"))
    )
    (net (code "12") (name "B") (class "Default")
      (node (ref "R22") (pin "2") (pinfunction "2_2") (pintype "passive"))
    )
    (net (code "13") (name "C") (class "Default")
      (node (ref "C1") (pin "+") (pinfunction "+_+") (pintype "passive"))
      (node (ref "IC1") (pin "1") (pinfunction "VI_1") (pintype "input"))
      (node (ref "R1") (pin "2") (pinfunction "2_2") (pintype "passive"))
      (node (ref "R49") (pin "2") (pinfunction "2_2") (pintype "passive"))
      (node (ref "R95") (pin "2") (pinfunction "2_2") (pintype "passive"))
      (node (ref "T1") (pin "2") (pinfunction "C_2") (pintype "passive"))
    )
    (net (code "14") (name "CH(+)") (class "Default")
      (node (ref "2K/1W") (pin "1") (pinfunction "1_1") (pintype "passive"))
      (node (ref "D10") (pin "A") (pinfunction "A_A") (pintype "passive"))
      (node (ref "D11") (pin "C") (pinfunction "C_C") (pintype "passive"))
    )
    (net (code "15") (name "CH1(-)") (class "Default")
      (node (ref "R9") (pin "2") (pinfunction "S_2") (pintype "passive"))
    )
    (net (code "16") (name "CH5") (class "Default")
      (node (ref "R113") (pin "1") (pinfunction "1_1") (pintype "passive"))
      (node (ref "R126") (pin "2") (pinfunction "S_2") (pintype "passive"))
      (node (ref "R126") (pin "3") (pinfunction "E_3") (pintype "passive"))
      (node (ref "R127") (pin "1") (pinfunction "1_1") (pintype "passive"))
      (node (ref "R67") (pin "1") (pinfunction "1_1") (pintype "passive"))
      (node (ref "R79") (pin "1") (pinfunction "1_1") (pintype "passive"))
      (node (ref "R81") (pin "2") (pinfunction "S_2") (pintype "passive"))
      (node (ref "R81") (pin "3") (pinfunction "E_3") (pintype "passive"))
    )
    (net (code "17") (name "D") (class "Default")
      (node (ref "C2") (pin "-") (pinfunction "-_-") (pintype "passive"))
      (node (ref "IC2") (pin "1") (pinfunction "VI_1") (pintype "input"))
      (node (ref "Q1") (pin "2") (pinfunction "C_2") (pintype "passive"))
      (node (ref "R130") (pin "1") (pinfunction "1_1") (pintype "passive"))
      (node (ref "R136") (pin "1") (pinfunction "1_1") (pintype "passive"))
      (node (ref "R141") (pin "1") (pinfunction "1_1") (pintype "passive"))
      (node (ref "R2") (pin "2") (pinfunction "2_2") (pintype "passive"))
      (node (ref "R84") (pin "1") (pinfunction "1_1") (pintype "passive"))
    )
    (net (code "18") (name "E") (class "Default")
      (node (ref "R127") (pin "2") (pinfunction "2_2") (pintype "passive"))
      (node (ref "R79") (pin "2") (pinfunction "2_2") (pintype "passive"))
    )
    (net (code "19") (name "F") (class "Default")
      (node (ref "R105") (pin "1") (pinfunction "1_1") (pintype "passive"))
      (node (ref "R59") (pin "1") (pinfunction "1_1") (pintype "passive"))
    )
    (net (code "20") (name "G") (class "Default")
      (node (ref "R108") (pin "2") (pinfunction "2_2") (pintype "passive"))
      (node (ref "R109") (pin "2") (pinfunction "2_2") (pintype "passive"))
      (node (ref "R119") (pin "2") (pinfunction "2_2") (pintype "passive"))
      (node (ref "R120") (pin "2") (pinfunction "2_2") (pintype "passive"))
      (node (ref "R62") (pin "2") (pinfunction "2_2") (pintype "passive"))
      (node (ref "R63") (pin "2") (pinfunction "2_2") (pintype "passive"))
      (node (ref "R73") (pin "2") (pinfunction "2_2") (pintype "passive"))
      (node (ref "R74") (pin "2") (pinfunction "2_2") (pintype "passive"))
      (node (ref "TR2") (pin "5") (pinfunction "5_5") (pintype "passive"))
    )
    (net (code "21") (name "I") (class "Default")
      (node (ref "TR2") (pin "8") (pinfunction "3_8") (pintype "passive"))
    )
    (net (code "22") (name "J") (class "Default")
      (node (ref "C48") (pin "1") (pinfunction "1_1") (pintype "passive"))
      (node (ref "R133") (pin "1") (pinfunction "1_1") (pintype "passive"))
      (node (ref "R149") (pin "2") (pinfunction "2_2") (pintype "passive"))
      (node (ref "R164") (pin "2") (pinfunction "2_2") (pintype "passive"))
      (node (ref "R41") (pin "2") (pinfunction "2_2") (pintype "passive"))
      (node (ref "R43") (pin "1") (pinfunction "1_1") (pintype "passive"))
    )
    (net (code "23") (name "K") (class "Default")
      (node (ref "IC13") (pin "6") (pinfunction "OUT_6") (pintype "output"))
      (node (ref "R134") (pin "2") (pinfunction "2_2") (pintype "passive"))
      (node (ref "R89") (pin "1") (pinfunction "1_1") (pintype "passive"))
    )
    (net (code "24") (name "M") (class "Default")
      (node (ref "D37") (pin "C") (pinfunction "C_C") (pintype "passive"))
      (node (ref "D54") (pin "C") (pinfunction "C_C") (pintype "passive"))
      (node (ref "IC16") (pin "6") (pinfunction "O_6") (pintype "output"))
      (node (ref "IC19") (pin "6") (pinfunction "O_6") (pintype "output"))
    )
    (net (code "25") (name "N$9") (class "Default")
      (node (ref "R10") (pin "1") (pinfunction "1_1") (pintype "passive"))
      (node (ref "R9") (pin "3") (pinfunction "E_3") (pintype "passive"))
    )
    (net (code "26") (name "N$199") (class "Default")
      (node (ref "IC15") (pin "5") (pinfunction "I0_5") (pintype "input"))
      (node (ref "IC18") (pin "6") (pinfunction "I1_6") (pintype "input"))
    )
    (net (code "27") (name "Net-(2K/1W1-Pad2)") (class "Default")
      (node (ref "2K/1W1") (pin "2") (pinfunction "2_2") (pintype "passive"))
      (node (ref "2K/1W2") (pin "2") (pinfunction "2_2") (pintype "passive"))
      (node (ref "2K/1W3") (pin "2") (pinfunction "2_2") (pintype "passive"))
    )
    (net (code "28") (name "Net-(2K/1W4-Pad2)") (class "Default")
      (node (ref "2K/1W4") (pin "2") (pinfunction "2_2") (pintype "passive"))
      (node (ref "2K/1W5") (pin "2") (pinfunction "2_2") (pintype "passive"))
      (node (ref "2K/1W6") (pin "2") (pinfunction "2_2") (pintype "passive"))
    )
    (net (code "29") (name "Net-(2K/1W7-Pad2)") (class "Default")
      (node (ref "2K/1W7") (pin "2") (pinfunction "2_2") (pintype "passive"))
      (node (ref "2K/1W8") (pin "2") (pinfunction "2_2") (pintype "passive"))
      (node (ref "2K/1W9") (pin "2") (pinfunction "2_2") (pintype "passive"))
    )
    (net (code "30") (name "Net-(2K/1W10-Pad2)") (class "Default")
      (node (ref "2K/1W10") (pin "2") (pinfunction "2_2") (pintype "passive"))
      (node (ref "2K/1W11") (pin "2") (pinfunction "2_2") (pintype "passive"))
      (node (ref "2K/1W12") (pin "2") (pinfunction "2_2") (pintype "passive"))
    )
    (net (code "31") (name "Net-(C31-Pad1)") (class "Default")
      (node (ref "C31") (pin "1") (pinfunction "1_1") (pintype "passive"))
      (node (ref "R5") (pin "1") (pinfunction "1_1") (pintype "passive"))
    )
    (net (code "32") (name "Net-(C35-Pad1)") (class "Default")
      (node (ref "C35") (pin "1") (pinfunction "1_1") (pintype "passive"))
      (node (ref "D1") (pin "A") (pinfunction "A_A") (pintype "passive"))
      (node (ref "D3") (pin "C") (pinfunction "C_C") (pintype "passive"))
      (node (ref "R5") (pin "2") (pinfunction "2_2") (pintype "passive"))
      (node (ref "TR1") (pin "5") (pinfunction "5_5") (pintype "passive"))
    )
    (net (code "33") (name "Net-(C35-Pad2)") (class "Default")
      (node (ref "C35") (pin "2") (pinfunction "2_2") (pintype "passive"))
      (node (ref "R6") (pin "2") (pinfunction "2_2") (pintype "passive"))
    )
    (net (code "34") (name "Net-(C37-Pad1)") (class "Default")
      (node (ref "C37") (pin "1") (pinfunction "1_1") (pintype "passive"))
      (node (ref "R11") (pin "2") (pinfunction "2_2") (pintype "passive"))
      (node (ref "R12") (pin "1") (pinfunction "1_1") (pintype "passive"))
    )
    (net (code "35") (name "Net-(C38-Pad1)") (class "Default")
      (node (ref "C38") (pin "1") (pinfunction "1_1") (pintype "passive"))
      (node (ref "R21") (pin "2") (pinfunction "2_2") (pintype "passive"))
      (node (ref "R22") (pin "1") (pinfunction "1_1") (pintype "passive"))
    )
    (net (code "36") (name "Net-(C42-Pad1)") (class "Default")
      (node (ref "C42") (pin "1") (pinfunction "1_1") (pintype "passive"))
      (node (ref "D17") (pin "C") (pinfunction "C_C") (pintype "passive"))
      (node (ref "R29") (pin "2") (pinfunction "2_2") (pintype "passive"))
    )
    (net (code "37") (name "Net-(C42-Pad2)") (class "Default")
      (node (ref "C42") (pin "2") (pinfunction "2_2") (pintype "passive"))
      (node (ref "D18") (pin "C") (pinfunction "C_C") (pintype "passive"))
      (node (ref "R30") (pin "2") (pinfunction "2_2") (pintype "passive"))
    )
    (net (code "38") (name "Net-(C45-Pad2)") (class "Default")
      (node (ref "C45") (pin "2") (pinfunction "2_2") (pintype "passive"))
      (node (ref "D19") (pin "C") (pinfunction "C_C") (pintype "passive"))
      (node (ref "D21") (pin "A") (pinfunction "A_A") (pintype "passive"))
    )
    (net (code "39") (name "Net-(C46-Pad1)") (class "Default")
      (node (ref "C46") (pin "1") (pinfunction "1_1") (pintype "passive"))
      (node (ref "D20") (pin "C") (pinfunction "C_C") (pintype "passive"))
      (node (ref "D22") (pin "A") (pinfunction "A_A") (pintype "passive"))
    )
    (net (code "40") (name "Net-(C49-Pad1)") (class "Default")
      (node (ref "C49") (pin "1") (pinfunction "1_1") (pintype "passive"))
      (node (ref "R44") (pin "1") (pinfunction "1_1") (pintype "passive"))
      (node (ref "R45") (pin "2") (pinfunction "2_2") (pintype "passive"))
    )
    (net (code "41") (name "Net-(C50-Pad1)") (class "Default")
      (node (ref "C50") (pin "1") (pinfunction "1_1") (pintype "passive"))
      (node (ref "D29") (pin "A") (pinfunction "A_A") (pintype "passive"))
      (node (ref "D30") (pin "C") (pinfunction "C_C") (pintype "passive"))
      (node (ref "R61") (pin "2") (pinfunction "2_2") (pintype "passive"))
      (node (ref "R65") (pin "2") (pinfunction "2_2") (pintype "passive"))
      (node (ref "T12") (pin "G") (pinfunction "G_G") (pintype "passive"))
    )
    (net (code "42") (name "Net-(C53-Pad1)") (class "Default")
      (node (ref "C53") (pin "1") (pinfunction "1_1") (pintype "passive"))
      (node (ref "D33") (pin "A") (pinfunction "A_A") (pintype "passive"))
      (node (ref "D34") (pin "C") (pinfunction "C_C") (pintype "passive"))
      (node (ref "R72") (pin "2") (pinfunction "2_2") (pintype "passive"))
      (node (ref "R76") (pin "2") (pinfunction "2_2") (pintype "passive"))
      (node (ref "T13") (pin "G") (pinfunction "G_G") (pintype "passive"))
    )
    (net (code "43") (name "Net-(C57-Pad1)") (class "Default")
      (node (ref "C57") (pin "1") (pinfunction "1_1") (pintype "passive"))
      (node (ref "R90") (pin "1") (pinfunction "1_1") (pintype "passive"))
      (node (ref "R91") (pin "2") (pinfunction "2_2") (pintype "passive"))
    )
    (net (code "44") (name "Net-(C58-Pad1)") (class "Default")
      (node (ref "C58") (pin "1") (pinfunction "1_1") (pintype "passive"))
      (node (ref "D46") (pin "A") (pinfunction "A_A") (pintype "passive"))
      (node (ref "D47") (pin "C") (pinfunction "C_C") (pintype "passive"))
      (node (ref "R107") (pin "2") (pinfunction "2_2") (pintype "passive"))
      (node (ref "R111") (pin "2") (pinfunction "2_2") (pintype "passive"))
      (node (ref "T14") (pin "G") (pinfunction "G_G") (pintype "passive"))
    )
    (net (code "45") (name "Net-(C61-Pad1)") (class "Default")
      (node (ref "C61") (pin "1") (pinfunction "1_1") (pintype "passive"))
      (node (ref "D50") (pin "A") (pinfunction "A_A") (pintype "passive"))
      (node (ref "D51") (pin "C") (pinfunction "C_C") (pintype "passive"))
      (node (ref "R118") (pin "2") (pinfunction "2_2") (pintype "passive"))
      (node (ref "R122") (pin "2") (pinfunction "2_2") (pintype "passive"))
      (node (ref "T15") (pin "G") (pinfunction "G_G") (pintype "passive"))
    )
    (net (code "46") (name "Net-(C65-Pad1)") (class "Default")
      (node (ref "C65") (pin "1") (pinfunction "1_1") (pintype "passive"))
      (node (ref "R149") (pin "1") (pinfunction "1_1") (pintype "passive"))
      (node (ref "R150") (pin "2") (pinfunction "2_2") (pintype "passive"))
    )
    (net (code "47") (name "Net-(C66-Pad1)") (class "Default")
      (node (ref "C66") (pin "1") (pinfunction "1_1") (pintype "passive"))
      (node (ref "R153") (pin "2") (pinfunction "2_2") (pintype "passive"))
      (node (ref "R154") (pin "1") (pinfunction "1_1") (pintype "passive"))
    )
    (net (code "48") (name "Net-(C67-Pad1)") (class "Default")
      (node (ref "C67") (pin "1") (pinfunction "1_1") (pintype "passive"))
      (node (ref "R155") (pin "2") (pinfunction "2_2") (pintype "passive"))
      (node (ref "R156") (pin "1") (pinfunction "1_1") (pintype "passive"))
      (node (ref "R157") (pin "2") (pinfunction "2_2") (pintype "passive"))
    )
    (net (code "49") (name "Net-(C68-Pad1)") (class "Default")
      (node (ref "C68") (pin "1") (pinfunction "1_1") (pintype "passive"))
      (node (ref "R158") (pin "1") (pinfunction "1_1") (pintype "passive"))
      (node (ref "R159") (pin "2") (pinfunction "2_2") (pintype "passive"))
    )
    (net (code "50") (name "Net-(C69-Pad1)") (class "Default")
      (node (ref "C69") (pin "1") (pinfunction "1_1") (pintype "passive"))
      (node (ref "R164") (pin "1") (pinfunction "1_1") (pintype "passive"))
      (node (ref "R165") (pin "2") (pinfunction "2_2") (pintype "passive"))
    )
    (net (code "51") (name "Net-(C70-Pad1)") (class "Default")
      (node (ref "C70") (pin "1") (pinfunction "1_1") (pintype "passive"))
      (node (ref "R168") (pin "2") (pinfunction "2_2") (pintype "passive"))
      (node (ref "R169") (pin "1") (pinfunction "1_1") (pintype "passive"))
    )
    (net (code "52") (name "Net-(C71-Pad1)") (class "Default")
      (node (ref "C71") (pin "1") (pinfunction "1_1") (pintype "passive"))
      (node (ref "R170") (pin "2") (pinfunction "2_2") (pintype "passive"))
      (node (ref "R171") (pin "1") (pinfunction "1_1") (pintype "passive"))
      (node (ref "R172") (pin "2") (pinfunction "2_2") (pintype "passive"))
    )
    (net (code "53") (name "Net-(C72-Pad1)") (class "Default")
      (node (ref "C72") (pin "1") (pinfunction "1_1") (pintype "passive"))
      (node (ref "R173") (pin "1") (pinfunction "1_1") (pintype "passive"))
      (node (ref "R174") (pin "2") (pinfunction "2_2") (pintype "passive"))
    )
    (net (code "54") (name "Net-(C73-Pad1)") (class "Default")
      (node (ref "C73") (pin "1") (pinfunction "1_1") (pintype "passive"))
      (node (ref "D65") (pin "A") (pinfunction "A_A") (pintype "passive"))
      (node (ref "R177") (pin "1") (pinfunction "1_1") (pintype "passive"))
    )
    (net (code "55") (name "Net-(D1-PadC)") (class "Default")
      (node (ref "D1") (pin "C") (pinfunction "C_C") (pintype "passive"))
      (node (ref "D2") (pin "C") (pinfunction "C_C") (pintype "passive"))
      (node (ref "R1") (pin "1") (pinfunction "1_1") (pintype "passive"))
    )
    (net (code "56") (name "Net-(D3-PadA)") (class "Default")
      (node (ref "D3") (pin "A") (pinfunction "A_A") (pintype "passive"))
      (node (ref "D4") (pin "A") (pinfunction "A_A") (pintype "passive"))
      (node (ref "R2") (pin "1") (pinfunction "1_1") (pintype "passive"))
    )
    (net (code "57") (name "Net-(D7-PadA)") (class "Default")
      (node (ref "D7") (pin "A") (pinfunction "A_A") (pintype "passive"))
      (node (ref "D8") (pin "C") (pinfunction "C_C") (pintype "passive"))
    )
    (net (code "58") (name "Net-(D8-PadA)") (class "Default")
      (node (ref "D8") (pin "A") (pinfunction "A_A") (pintype "passive"))
      (node (ref "D9") (pin "C") (pinfunction "C_C") (pintype "passive"))
    )
    (net (code "59") (name "Net-(D10-PadC)") (class "Default")
      (node (ref "D10") (pin "C") (pinfunction "C_C") (pintype "passive"))
      (node (ref "D9") (pin "A") (pinfunction "A_A") (pintype "passive"))
    )
    (net (code "60") (name "Net-(D11-PadA)") (class "Default")
      (node (ref "D11") (pin "A") (pinfunction "A_A") (pintype "passive"))
      (node (ref "D12") (pin "C") (pinfunction "C_C") (pintype "passive"))
    )
    (net (code "61") (name "Net-(D12-PadA)") (class "Default")
      (node (ref "D12") (pin "A") (pinfunction "A_A") (pintype "passive"))
      (node (ref "D13") (pin "C") (pinfunction "C_C") (pintype "passive"))
    )
    (net (code "62") (name "Net-(D13-PadA)") (class "Default")
      (node (ref "D13") (pin "A") (pinfunction "A_A") (pintype "passive"))
      (node (ref "D14") (pin "C") (pinfunction "C_C") (pintype "passive"))
    )
    (net (code "63") (name "Net-(D16-PadC)") (class "Default")
      (node (ref "D16") (pin "C") (pinfunction "C_C") (pintype "passive"))
      (node (ref "R21") (pin "1") (pinfunction "1_1") (pintype "passive"))
      (node (ref "R23") (pin "2") (pinfunction "2_2") (pintype "passive"))
    )
    (net (code "64") (name "Net-(D23-PadC)") (class "Default")
      (node (ref "D23") (pin "C") (pinfunction "C_C") (pintype "passive"))
      (node (ref "D24") (pin "C") (pinfunction "C_C") (pintype "passive"))
    )
    (net (code "65") (name "Net-(D25-PadC)") (class "Default")
      (node (ref "D25") (pin "C") (pinfunction "C_C") (pintype "passive"))
      (node (ref "D26") (pin "C") (pinfunction "C_C") (pintype "passive"))
    )
    (net (code "66") (name "Net-(D29-PadC)") (class "Default")
      (node (ref "D29") (pin "C") (pinfunction "C_C") (pintype "passive"))
      (node (ref "R62") (pin "1") (pinfunction "1_1") (pintype "passive"))
    )
    (net (code "67") (name "Net-(D31-PadC)") (class "Default")
      (node (ref "D31") (pin "C") (pinfunction "C_C") (pintype "passive"))
      (node (ref "R64") (pin "1") (pinfunction "1_1") (pintype "passive"))
      (node (ref "TR3") (pin "1") (pinfunction "1_1") (pintype "passive"))
    )
    (net (code "68") (name "Net-(D33-PadC)") (class "Default")
      (node (ref "D33") (pin "C") (pinfunction "C_C") (pintype "passive"))
      (node (ref "R73") (pin "1") (pinfunction "1_1") (pintype "passive"))
    )
    (net (code "69") (name "Net-(D35-PadC)") (class "Default")
      (node (ref "D35") (pin "C") (pinfunction "C_C") (pintype "passive"))
      (node (ref "R75") (pin "1") (pinfunction "1_1") (pintype "passive"))
      (node (ref "TR4") (pin "1") (pinfunction "1_1") (pintype "passive"))
    )
    (net (code "70") (name "Net-(D37-PadA)") (class "Default")
      (node (ref "D37") (pin "A") (pinfunction "A_A") (pintype "passive"))
      (node (ref "R80") (pin "2") (pinfunction "2_2") (pintype "passive"))
    )
    (net (code "71") (name "Net-(D39-PadA)") (class "Default")
      (node (ref "D39") (pin "A") (pinfunction "A_A") (pintype "passive"))
      (node (ref "R45") (pin "1") (pinfunction "1_1") (pintype "passive"))
    )
    (net (code "72") (name "Net-(D40-PadC)") (class "Default")
      (node (ref "D40") (pin "C") (pinfunction "C_C") (pintype "passive"))
      (node (ref "D41") (pin "C") (pinfunction "C_C") (pintype "passive"))
    )
    (net (code "73") (name "Net-(D42-PadC)") (class "Default")
      (node (ref "D42") (pin "C") (pinfunction "C_C") (pintype "passive"))
      (node (ref "D43") (pin "C") (pinfunction "C_C") (pintype "passive"))
    )
    (net (code "74") (name "Net-(D46-PadC)") (class "Default")
      (node (ref "D46") (pin "C") (pinfunction "C_C") (pintype "passive"))
      (node (ref "R108") (pin "1") (pinfunction "1_1") (pintype "passive"))
    )
    (net (code "75") (name "Net-(D48-PadC)") (class "Default")
      (node (ref "D48") (pin "C") (pinfunction "C_C") (pintype "passive"))
      (node (ref "R110") (pin "1") (pinfunction "1_1") (pintype "passive"))
      (node (ref "TR5") (pin "1") (pinfunction "1_1") (pintype "passive"))
    )
    (net (code "76") (name "Net-(D50-PadC)") (class "Default")
      (node (ref "D50") (pin "C") (pinfunction "C_C") (pintype "passive"))
      (node (ref "R119") (pin "1") (pinfunction "1_1") (pintype "passive"))
    )
    (net (code "77") (name "Net-(D52-PadC)") (class "Default")
      (node (ref "D52") (pin "C") (pinfunction "C_C") (pintype "passive"))
      (node (ref "R121") (pin "1") (pinfunction "1_1") (pintype "passive"))
      (node (ref "TR6") (pin "1") (pinfunction "1_1") (pintype "passive"))
    )
    (net (code "78") (name "Net-(D54-PadA)") (class "Default")
      (node (ref "D54") (pin "A") (pinfunction "A_A") (pintype "passive"))
      (node (ref "R125") (pin "2") (pinfunction "2_2") (pintype "passive"))
    )
    (net (code "79") (name "Net-(D56-PadA)") (class "Default")
      (node (ref "D56") (pin "A") (pinfunction "A_A") (pintype "passive"))
      (node (ref "R91") (pin "1") (pinfunction "1_1") (pintype "passive"))
    )
    (net (code "80") (name "Net-(D60-PadC)") (class "Default")
      (node (ref "D60") (pin "C") (pinfunction "C_C") (pintype "passive"))
      (node (ref "R152") (pin "1") (pinfunction "1_1") (pintype "passive"))
      (node (ref "R153") (pin "1") (pinfunction "1_1") (pintype "passive"))
    )
    (net (code "81") (name "Net-(D61-PadC)") (class "Default")
      (node (ref "D61") (pin "C") (pinfunction "C_C") (pintype "passive"))
      (node (ref "R157") (pin "1") (pinfunction "1_1") (pintype "passive"))
    )
    (net (code "82") (name "Net-(D63-PadC)") (class "Default")
      (node (ref "D63") (pin "C") (pinfunction "C_C") (pintype "passive"))
      (node (ref "R167") (pin "1") (pinfunction "1_1") (pintype "passive"))
      (node (ref "R168") (pin "1") (pinfunction "1_1") (pintype "passive"))
    )
    (net (code "83") (name "Net-(D64-PadC)") (class "Default")
      (node (ref "D64") (pin "C") (pinfunction "C_C") (pintype "passive"))
      (node (ref "R172") (pin "1") (pinfunction "1_1") (pintype "passive"))
    )
    (net (code "84") (name "Net-(D65-PadC)") (class "Default")
      (node (ref "D65") (pin "C") (pinfunction "C_C") (pintype "passive"))
      (node (ref "R175") (pin "1") (pinfunction "1_1") (pintype "passive"))
      (node (ref "R176") (pin "2") (pinfunction "2_2") (pintype "passive"))
    )
    (net (code "85") (name "Net-(IC1-GND)") (class "Default")
      (node (ref "D5") (pin "A") (pinfunction "A_A") (pintype "passive"))
      (node (ref "IC1") (pin "2") (pinfunction "GND_2") (pintype "passive"))
    )
    (net (code "86") (name "Net-(IC1-VO)") (class "Default")
      (node (ref "IC1") (pin "3") (pinfunction "VO_3") (pintype "passive"))
      (node (ref "T1") (pin "3") (pinfunction "B_3") (pintype "passive"))
    )
    (net (code "87") (name "Net-(IC2-GND)") (class "Default")
      (node (ref "D6") (pin "C") (pinfunction "C_C") (pintype "passive"))
      (node (ref "IC2") (pin "2") (pinfunction "GND_2") (pintype "passive"))
    )
    (net (code "88") (name "Net-(IC2-VO)") (class "Default")
      (node (ref "IC2") (pin "3") (pinfunction "VO_3") (pintype "passive"))
      (node (ref "Q1") (pin "3") (pinfunction "B_3") (pintype "passive"))
    )
    (net (code "89") (name "Net-(IC3-+IN)") (class "Default")
      (node (ref "IC3") (pin "3") (pinfunction "+IN_3") (pintype "input"))
      (node (ref "R14") (pin "2") (pinfunction "2_2") (pintype "passive"))
    )
    (net (code "90") (name "Net-(IC3--IN)") (class "Default")
      (node (ref "IC3") (pin "2") (pinfunction "-IN_2") (pintype "input"))
      (node (ref "R12") (pin "2") (pinfunction "2_2") (pintype "passive"))
      (node (ref "R13") (pin "1") (pinfunction "1_1") (pintype "passive"))
    )
    (net (code "91") (name "Net-(IC3-OUT)") (class "Default")
      (node (ref "IC3") (pin "6") (pinfunction "OUT_6") (pintype "output"))
      (node (ref "R13") (pin "2") (pinfunction "2_2") (pintype "passive"))
      (node (ref "R15") (pin "1") (pinfunction "1_1") (pintype "passive"))
    )
    (net (code "92") (name "Net-(IC4-+IN)") (class "Default")
      (node (ref "IC4") (pin "3") (pinfunction "+IN_3") (pintype "input"))
      (node (ref "R17") (pin "2") (pinfunction "2_2") (pintype "passive"))
    )
    (net (code "93") (name "Net-(IC4--IN)") (class "Default")
      (node (ref "D15") (pin "A") (pinfunction "A_A") (pintype "passive"))
      (node (ref "IC4") (pin "2") (pinfunction "-IN_2") (pintype "input"))
      (node (ref "R15") (pin "2") (pinfunction "2_2") (pintype "passive"))
      (node (ref "R16") (pin "2") (pinfunction "2_2") (pintype "passive"))
    )
    (net (code "94") (name "Net-(IC4-OUT)") (class "Default")
      (node (ref "D15") (pin "C") (pinfunction "C_C") (pintype "passive"))
      (node (ref "D16") (pin "A") (pinfunction "A_A") (pintype "passive"))
      (node (ref "IC4") (pin "6") (pinfunction "OUT_6") (pintype "output"))
    )
    (net (code "95") (name "Net-(IC5--IN)") (class "Default")
      (node (ref "D23") (pin "A") (pinfunction "A_A") (pintype "passive"))
      (node (ref "IC5") (pin "2") (pinfunction "-IN_2") (pintype "input"))
      (node (ref "R42") (pin "2") (pinfunction "2_2") (pintype "passive"))
      (node (ref "R43") (pin "2") (pinfunction "2_2") (pintype "passive"))
      (node (ref "R44") (pin "2") (pinfunction "2_2") (pintype "passive"))
      (node (ref "R46") (pin "2") (pinfunction "2_2") (pintype "passive"))
      (node (ref "R47") (pin "1") (pinfunction "1_1") (pintype "passive"))
    )
    (net (code "96") (name "Net-(IC5-OUT)") (class "Default")
      (node (ref "D24") (pin "A") (pinfunction "A_A") (pintype "passive"))
      (node (ref "D25") (pin "A") (pinfunction "A_A") (pintype "passive"))
      (node (ref "IC5") (pin "6") (pinfunction "OUT_6") (pintype "output"))
      (node (ref "R47") (pin "2") (pinfunction "2_2") (pintype "passive"))
    )
    (net (code "97") (name "Net-(IC6--IN)") (class "Default")
      (node (ref "D28") (pin "A") (pinfunction "A_A") (pintype "passive"))
      (node (ref "IC6") (pin "2") (pinfunction "-IN_2") (pintype "input"))
      (node (ref "R53") (pin "2") (pinfunction "2_2") (pintype "passive"))
      (node (ref "R54") (pin "2") (pinfunction "2_2") (pintype "passive"))
      (node (ref "R55") (pin "2") (pinfunction "2_2") (pintype "passive"))
      (node (ref "R56") (pin "2") (pinfunction "2_2") (pintype "passive"))
    )
    (net (code "98") (name "Net-(IC6-OUT)") (class "Default")
      (node (ref "D28") (pin "C") (pinfunction "C_C") (pintype "passive"))
      (node (ref "IC6") (pin "6") (pinfunction "OUT_6") (pintype "output"))
      (node (ref "R61") (pin "1") (pinfunction "1_1") (pintype "passive"))
    )
    (net (code "99") (name "Net-(IC7--IN)") (class "Default")
      (node (ref "D32") (pin "A") (pinfunction "A_A") (pintype "passive"))
      (node (ref "IC7") (pin "2") (pinfunction "-IN_2") (pintype "input"))
      (node (ref "R66") (pin "2") (pinfunction "2_2") (pintype "passive"))
      (node (ref "R67") (pin "2") (pinfunction "2_2") (pintype "passive"))
      (node (ref "R68") (pin "2") (pinfunction "2_2") (pintype "passive"))
      (node (ref "R69") (pin "2") (pinfunction "2_2") (pintype "passive"))
    )
    (net (code "100") (name "Net-(IC7-OUT)") (class "Default")
      (node (ref "D32") (pin "C") (pinfunction "C_C") (pintype "passive"))
      (node (ref "IC7") (pin "6") (pinfunction "OUT_6") (pintype "output"))
      (node (ref "R72") (pin "1") (pinfunction "1_1") (pintype "passive"))
    )
    (net (code "101") (name "Net-(IC7-V-)") (class "Default")
      (node (ref "IC7") (pin "4") (pinfunction "V-_4") (pintype "power_in"))
      (node (ref "IC8") (pin "4") (pinfunction "V-_4") (pintype "power_in"))
      (node (ref "R86") (pin "1") (pinfunction "1_1") (pintype "passive"))
    )
    (net (code "102") (name "Net-(IC8-+IN)") (class "Default")
      (node (ref "IC8") (pin "3") (pinfunction "+IN_3") (pintype "input"))
      (node (ref "R82") (pin "1") (pinfunction "1_1") (pintype "passive"))
    )
    (net (code "103") (name "Net-(IC8--IN)") (class "Default")
      (node (ref "D38") (pin "C") (pinfunction "C_C") (pintype "passive"))
      (node (ref "IC8") (pin "2") (pinfunction "-IN_2") (pintype "input"))
      (node (ref "R83") (pin "2") (pinfunction "2_2") (pintype "passive"))
      (node (ref "R84") (pin "2") (pinfunction "2_2") (pintype "passive"))
    )
    (net (code "104") (name "Net-(IC8-OUT)") (class "Default")
      (node (ref "D38") (pin "A") (pinfunction "A_A") (pintype "passive"))
      (node (ref "D39") (pin "C") (pinfunction "C_C") (pintype "passive"))
      (node (ref "IC8") (pin "6") (pinfunction "OUT_6") (pintype "output"))
    )
    (net (code "105") (name "Net-(IC9--IN)") (class "Default")
      (node (ref "D40") (pin "A") (pinfunction "A_A") (pintype "passive"))
      (node (ref "IC9") (pin "2") (pinfunction "-IN_2") (pintype "input"))
      (node (ref "R88") (pin "2") (pinfunction "2_2") (pintype "passive"))
      (node (ref "R89") (pin "2") (pinfunction "2_2") (pintype "passive"))
      (node (ref "R90") (pin "2") (pinfunction "2_2") (pintype "passive"))
      (node (ref "R92") (pin "2") (pinfunction "2_2") (pintype "passive"))
      (node (ref "R93") (pin "1") (pinfunction "1_1") (pintype "passive"))
    )
    (net (code "106") (name "Net-(IC9-OUT)") (class "Default")
      (node (ref "D41") (pin "A") (pinfunction "A_A") (pintype "passive"))
      (node (ref "D42") (pin "A") (pinfunction "A_A") (pintype "passive"))
      (node (ref "IC9") (pin "6") (pinfunction "OUT_6") (pintype "output"))
      (node (ref "R93") (pin "2") (pinfunction "2_2") (pintype "passive"))
    )
    (net (code "107") (name "Net-(IC10--IN)") (class "Default")
      (node (ref "D45") (pin "A") (pinfunction "A_A") (pintype "passive"))
      (node (ref "IC10") (pin "2") (pinfunction "-IN_2") (pintype "input"))
      (node (ref "R100") (pin "2") (pinfunction "2_2") (pintype "passive"))
      (node (ref "R101") (pin "2") (pinfunction "2_2") (pintype "passive"))
      (node (ref "R102") (pin "2") (pinfunction "2_2") (pintype "passive"))
      (node (ref "R99") (pin "2") (pinfunction "2_2") (pintype "passive"))
    )
    (net (code "108") (name "Net-(IC10-OUT)") (class "Default")
      (node (ref "D45") (pin "C") (pinfunction "C_C") (pintype "passive"))
      (node (ref "IC10") (pin "6") (pinfunction "OUT_6") (pintype "output"))
      (node (ref "R107") (pin "1") (pinfunction "1_1") (pintype "passive"))
    )
    (net (code "109") (name "Net-(IC11--IN)") (class "Default")
      (node (ref "D49") (pin "A") (pinfunction "A_A") (pintype "passive"))
      (node (ref "IC11") (pin "2") (pinfunction "-IN_2") (pintype "input"))
      (node (ref "R112") (pin "2") (pinfunction "2_2") (pintype "passive"))
      (node (ref "R113") (pin "2") (pinfunction "2_2") (pintype "passive"))
      (node (ref "R114") (pin "2") (pinfunction "2_2") (pintype "passive"))
      (node (ref "R115") (pin "2") (pinfunction "2_2") (pintype "passive"))
    )
    (net (code "110") (name "Net-(IC11-OUT)") (class "Default")
      (node (ref "D49") (pin "C") (pinfunction "C_C") (pintype "passive"))
      (node (ref "IC11") (pin "6") (pinfunction "OUT_6") (pintype "output"))
      (node (ref "R118") (pin "1") (pinfunction "1_1") (pintype "passive"))
    )
    (net (code "111") (name "Net-(IC11-V-)") (class "Default")
      (node (ref "IC11") (pin "4") (pinfunction "V-_4") (pintype "power_in"))
      (node (ref "IC12") (pin "4") (pinfunction "V-_4") (pintype "power_in"))
      (node (ref "R132") (pin "1") (pinfunction "1_1") (pintype "passive"))
    )
    (net (code "112") (name "Net-(IC12-+IN)") (class "Default")
      (node (ref "IC12") (pin "3") (pinfunction "+IN_3") (pintype "input"))
      (node (ref "R128") (pin "1") (pinfunction "1_1") (pintype "passive"))
    )
    (net (code "113") (name "Net-(IC12--IN)") (class "Default")
      (node (ref "D55") (pin "C") (pinfunction "C_C") (pintype "passive"))
      (node (ref "IC12") (pin "2") (pinfunction "-IN_2") (pintype "input"))
      (node (ref "R129") (pin "2") (pinfunction "2_2") (pintype "passive"))
      (node (ref "R130") (pin "2") (pinfunction "2_2") (pintype "passive"))
    )
    (net (code "114") (name "Net-(IC12-OUT)") (class "Default")
      (node (ref "D55") (pin "A") (pinfunction "A_A") (pintype "passive"))
      (node (ref "D56") (pin "C") (pinfunction "C_C") (pintype "passive"))
      (node (ref "IC12") (pin "6") (pinfunction "OUT_6") (pintype "output"))
    )
    (net (code "115") (name "Net-(IC13-+IN)") (class "Default")
      (node (ref "IC13") (pin "3") (pinfunction "+IN_3") (pintype "input"))
      (node (ref "R87") (pin "2") (pinfunction "2_2") (pintype "passive"))
    )
    (net (code "116") (name "Net-(IC13--IN)") (class "Default")
      (node (ref "IC13") (pin "2") (pinfunction "-IN_2") (pintype "input"))
      (node (ref "R133") (pin "2") (pinfunction "2_2") (pintype "passive"))
      (node (ref "R134") (pin "1") (pinfunction "1_1") (pintype "passive"))
    )
    (net (code "117") (name "Net-(IC14-+IN)") (class "Default")
      (node (ref "IC14") (pin "3") (pinfunction "+IN_3") (pintype "input"))
      (node (ref "R151") (pin "1") (pinfunction "1_1") (pintype "passive"))
    )
    (net (code "118") (name "Net-(IC14--IN)") (class "Default")
      (node (ref "D59") (pin "A") (pinfunction "A_A") (pintype "passive"))
      (node (ref "IC14") (pin "2") (pinfunction "-IN_2") (pintype "input"))
      (node (ref "R147") (pin "1") (pinfunction "1_1") (pintype "passive"))
      (node (ref "R150") (pin "1") (pinfunction "1_1") (pintype "passive"))
    )
    (net (code "119") (name "Net-(IC14-OUT)") (class "Default")
      (node (ref "D59") (pin "C") (pinfunction "C_C") (pintype "passive"))
      (node (ref "D60") (pin "A") (pinfunction "A_A") (pintype "passive"))
      (node (ref "IC14") (pin "6") (pinfunction "OUT_6") (pintype "output"))
    )
    (net (code "120") (name "Net-(IC15A-I0)") (class "Default")
      (node (ref "IC15") (pin "1") (pinfunction "I0_1") (pintype "input"))
      (node (ref "IC18") (pin "11") (pinfunction "O_11") (pintype "output"))
      (node (ref "IC19") (pin "1") (pinfunction "I_1") (pintype "input"))
      (node (ref "IC19") (pin "5") (pinfunction "I_5") (pintype "input"))
    )
    (net (code "121") (name "Net-(IC15A-I1)") (class "Default")
      (node (ref "IC15") (pin "2") (pinfunction "I1_2") (pintype "input"))
      (node (ref "R156") (pin "2") (pinfunction "2_2") (pintype "passive"))
    )
    (net (code "122") (name "Net-(IC15A-O)") (class "Default")
      (node (ref "IC15") (pin "3") (pinfunction "O_3") (pintype "output"))
      (node (ref "R159") (pin "1") (pinfunction "1_1") (pintype "passive"))
    )
    (net (code "123") (name "Net-(IC15B-I1)") (class "Default")
      (node (ref "IC15") (pin "6") (pinfunction "I1_6") (pintype "input"))
      (node (ref "R154") (pin "2") (pinfunction "2_2") (pintype "passive"))
    )
    (net (code "124") (name "Net-(IC15B-O)") (class "Default")
      (node (ref "D61") (pin "A") (pinfunction "A_A") (pintype "passive"))
      (node (ref "IC15") (pin "4") (pinfunction "O_4") (pintype "output"))
      (node (ref "R155") (pin "1") (pinfunction "1_1") (pintype "passive"))
    )
    (net (code "125") (name "Net-(IC15C-I0)") (class "Default")
      (node (ref "IC15") (pin "8") (pinfunction "I0_8") (pintype "input"))
      (node (ref "IC15") (pin "9") (pinfunction "I1_9") (pintype "input"))
      (node (ref "R158") (pin "2") (pinfunction "2_2") (pintype "passive"))
    )
    (net (code "126") (name "Net-(IC15C-O)") (class "Default")
      (node (ref "IC15") (pin "10") (pinfunction "O_10") (pintype "output"))
      (node (ref "IC15") (pin "13") (pinfunction "I1_13") (pintype "input"))
    )
    (net (code "127") (name "Net-(IC15D-O)") (class "Default")
      (node (ref "IC15") (pin "11") (pinfunction "O_11") (pintype "output"))
      (node (ref "IC16") (pin "1") (pinfunction "I_1") (pintype "input"))
      (node (ref "IC16") (pin "5") (pinfunction "I_5") (pintype "input"))
      (node (ref "IC18") (pin "2") (pinfunction "I1_2") (pintype "input"))
    )
    (net (code "128") (name "Net-(IC16A-O)") (class "Default")
      (node (ref "IC16") (pin "2") (pinfunction "O_2") (pintype "output"))
      (node (ref "IC16") (pin "3") (pinfunction "I_3") (pintype "input"))
    )
    (net (code "129") (name "Net-(IC17-+IN)") (class "Default")
      (node (ref "IC17") (pin "3") (pinfunction "+IN_3") (pintype "input"))
      (node (ref "R166") (pin "1") (pinfunction "1_1") (pintype "passive"))
    )
    (net (code "130") (name "Net-(IC17--IN)") (class "Default")
      (node (ref "D62") (pin "A") (pinfunction "A_A") (pintype "passive"))
      (node (ref "IC17") (pin "2") (pinfunction "-IN_2") (pintype "input"))
      (node (ref "R162") (pin "1") (pinfunction "1_1") (pintype "passive"))
      (node (ref "R165") (pin "1") (pinfunction "1_1") (pintype "passive"))
    )
    (net (code "131") (name "Net-(IC17-OUT)") (class "Default")
      (node (ref "D62") (pin "C") (pinfunction "C_C") (pintype "passive"))
      (node (ref "D63") (pin "A") (pinfunction "A_A") (pintype "passive"))
      (node (ref "IC17") (pin "6") (pinfunction "OUT_6") (pintype "output"))
    )
    (net (code "132") (name "Net-(IC18A-I0)") (class "Default")
      (node (ref "IC18") (pin "1") (pinfunction "I0_1") (pintype "input"))
      (node (ref "R171") (pin "2") (pinfunction "2_2") (pintype "passive"))
    )
    (net (code "133") (name "Net-(IC18A-O)") (class "Default")
      (node (ref "IC18") (pin "3") (pinfunction "O_3") (pintype "output"))
      (node (ref "R174") (pin "1") (pinfunction "1_1") (pintype "passive"))
    )
    (net (code "134") (name "Net-(IC18B-I0)") (class "Default")
      (node (ref "IC18") (pin "5") (pinfunction "I0_5") (pintype "input"))
      (node (ref "R169") (pin "2") (pinfunction "2_2") (pintype "passive"))
    )
    (net (code "135") (name "Net-(IC18B-O)") (class "Default")
      (node (ref "D64") (pin "A") (pinfunction "A_A") (pintype "passive"))
      (node (ref "IC18") (pin "4") (pinfunction "O_4") (pintype "output"))
      (node (ref "R170") (pin "1") (pinfunction "1_1") (pintype "passive"))
    )
    (net (code "136") (name "Net-(IC18C-I0)") (class "Default")
      (node (ref "IC18") (pin "8") (pinfunction "I0_8") (pintype "input"))
      (node (ref "IC18") (pin "9") (pinfunction "I1_9") (pintype "input"))
      (node (ref "R173") (pin "2") (pinfunction "2_2") (pintype "passive"))
    )
    (net (code "137") (name "Net-(IC18C-O)") (class "Default")
      (node (ref "IC18") (pin "10") (pinfunction "O_10") (pintype "output"))
      (node (ref "IC18") (pin "13") (pinfunction "I1_13") (pintype "input"))
    )
    (net (code "138") (name "Net-(IC18D-I0)") (class "Default")
      (node (ref "IC18") (pin "12") (pinfunction "I0_12") (pintype "input"))
      (node (ref "R175") (pin "2") (pinfunction "2_2") (pintype "passive"))
    )
    (net (code "139") (name "Net-(IC19A-O)") (class "Default")
      (node (ref "IC19") (pin "2") (pinfunction "O_2") (pintype "output"))
      (node (ref "IC19") (pin "3") (pinfunction "I_3") (pintype "input"))
    )
    (net (code "140") (name "Net-(Q1-E)") (class "Default")
      (node (ref "Q1") (pin "1") (pinfunction "E_1") (pintype "passive"))
      (node (ref "R4") (pin "1") (pinfunction "1_1") (pintype "passive"))
    )
    (net (code "141") (name "Net-(Q2-B)") (class "Default")
      (node (ref "C41") (pin "2") (pinfunction "2_2") (pintype "passive"))
      (node (ref "Q2") (pin "3") (pinfunction "B_3") (pintype "passive"))
      (node (ref "R28") (pin "2") (pinfunction "2_2") (pintype "passive"))
      (node (ref "R31") (pin "2") (pinfunction "2_2") (pintype "passive"))
    )
    (net (code "142") (name "Net-(Q2-C)") (class "Default")
      (node (ref "C40") (pin "2") (pinfunction "2_2") (pintype "passive"))
      (node (ref "C45") (pin "1") (pinfunction "1_1") (pintype "passive"))
      (node (ref "C46") (pin "2") (pinfunction "2_2") (pintype "passive"))
      (node (ref "Q2") (pin "2") (pinfunction "C_2") (pintype "passive"))
      (node (ref "R26") (pin "2") (pinfunction "2_2") (pintype "passive"))
      (node (ref "R27") (pin "2") (pinfunction "2_2") (pintype "passive"))
    )
    (net (code "143") (name "Net-(Q2-E)") (class "Default")
      (node (ref "D18") (pin "A") (pinfunction "A_A") (pintype "passive"))
      (node (ref "Q2") (pin "1") (pinfunction "E_1") (pintype "passive"))
    )
    (net (code "144") (name "Net-(Q3-B)") (class "Default")
      (node (ref "C40") (pin "1") (pinfunction "1_1") (pintype "passive"))
      (node (ref "Q3") (pin "3") (pinfunction "B_3") (pintype "passive"))
      (node (ref "R27") (pin "1") (pinfunction "1_1") (pintype "passive"))
      (node (ref "R32") (pin "2") (pinfunction "2_2") (pintype "passive"))
    )
    (net (code "145") (name "Net-(Q3-C)") (class "Default")
      (node (ref "C41") (pin "1") (pinfunction "1_1") (pintype "passive"))
      (node (ref "Q3") (pin "2") (pinfunction "C_2") (pintype "passive"))
      (node (ref "R25") (pin "2") (pinfunction "2_2") (pintype "passive"))
      (node (ref "R28") (pin "1") (pinfunction "1_1") (pintype "passive"))
    )
    (net (code "146") (name "Net-(Q3-E)") (class "Default")
      (node (ref "D17") (pin "A") (pinfunction "A_A") (pintype "passive"))
      (node (ref "Q3") (pin "1") (pinfunction "E_1") (pintype "passive"))
    )
    (net (code "147") (name "Net-(Q4-B)") (class "Default")
      (node (ref "C44") (pin "1") (pinfunction "1_1") (pintype "passive"))
      (node (ref "D22") (pin "C") (pinfunction "C_C") (pintype "passive"))
      (node (ref "Q4") (pin "3") (pinfunction "B_3") (pintype "passive"))
      (node (ref "Q5") (pin "3") (pinfunction "B_3") (pintype "passive"))
      (node (ref "R34") (pin "2") (pinfunction "2_2") (pintype "passive"))
      (node (ref "R36") (pin "2") (pinfunction "2_2") (pintype "passive"))
      (node (ref "T10") (pin "2") (pinfunction "C_2") (pintype "passive"))
    )
    (net (code "148") (name "Net-(Q4-C)") (class "Default")
      (node (ref "Q4") (pin "2") (pinfunction "C_2") (pintype "passive"))
      (node (ref "R40") (pin "2") (pinfunction "2_2") (pintype "passive"))
    )
    (net (code "149") (name "Net-(Q4-E)") (class "Default")
      (node (ref "C47") (pin "+") (pinfunction "+_+") (pintype "passive"))
      (node (ref "Q4") (pin "1") (pinfunction "E_1") (pintype "passive"))
      (node (ref "Q5") (pin "1") (pinfunction "E_1") (pintype "passive"))
    )
    (net (code "150") (name "Net-(Q5-C)") (class "Default")
      (node (ref "C39") (pin "+") (pinfunction "+_+") (pintype "passive"))
      (node (ref "Q5") (pin "2") (pinfunction "C_2") (pintype "passive"))
      (node (ref "R24") (pin "1") (pinfunction "1_1") (pintype "passive"))
      (node (ref "R25") (pin "1") (pinfunction "1_1") (pintype "passive"))
      (node (ref "R26") (pin "1") (pinfunction "1_1") (pintype "passive"))
      (node (ref "R33") (pin "1") (pinfunction "1_1") (pintype "passive"))
      (node (ref "R34") (pin "1") (pinfunction "1_1") (pintype "passive"))
    )
    (net (code "151") (name "Net-(Q6-B)") (class "Default")
      (node (ref "Q6") (pin "3") (pinfunction "B_3") (pintype "passive"))
      (node (ref "R50") (pin "1") (pinfunction "1_1") (pintype "passive"))
      (node (ref "R52") (pin "2") (pinfunction "2_2") (pintype "passive"))
    )
    (net (code "152") (name "Net-(Q6-C)") (class "Default")
      (node (ref "D26") (pin "A") (pinfunction "A_A") (pintype "passive"))
      (node (ref "D27") (pin "A") (pinfunction "A_A") (pintype "passive"))
      (node (ref "Q6") (pin "2") (pinfunction "C_2") (pintype "passive"))
      (node (ref "R53") (pin "1") (pinfunction "1_1") (pintype "passive"))
      (node (ref "R66") (pin "1") (pinfunction "1_1") (pintype "passive"))
    )
    (net (code "153") (name "Net-(Q6-E)") (class "Default")
      (node (ref "Q6") (pin "1") (pinfunction "E_1") (pintype "passive"))
      (node (ref "R51") (pin "1") (pinfunction "1_1") (pintype "passive"))
    )
    (net (code "154") (name "Net-(Q7-B)") (class "Default")
      (node (ref "D36") (pin "C") (pinfunction "C_C") (pintype "passive"))
      (node (ref "Q7") (pin "3") (pinfunction "B_3") (pintype "passive"))
      (node (ref "R80") (pin "1") (pinfunction "1_1") (pintype "passive"))
    )
    (net (code "155") (name "Net-(Q7-E)") (class "Default")
      (node (ref "Q7") (pin "1") (pinfunction "E_1") (pintype "passive"))
      (node (ref "R77") (pin "1") (pinfunction "1_1") (pintype "passive"))
    )
    (net (code "156") (name "Net-(Q8-B)") (class "Default")
      (node (ref "Q8") (pin "3") (pinfunction "B_3") (pintype "passive"))
      (node (ref "R96") (pin "1") (pinfunction "1_1") (pintype "passive"))
      (node (ref "R98") (pin "2") (pinfunction "2_2") (pintype "passive"))
    )
    (net (code "157") (name "Net-(Q8-C)") (class "Default")
      (node (ref "D43") (pin "A") (pinfunction "A_A") (pintype "passive"))
      (node (ref "D44") (pin "A") (pinfunction "A_A") (pintype "passive"))
      (node (ref "Q8") (pin "2") (pinfunction "C_2") (pintype "passive"))
      (node (ref "R112") (pin "1") (pinfunction "1_1") (pintype "passive"))
      (node (ref "R99") (pin "1") (pinfunction "1_1") (pintype "passive"))
    )
    (net (code "158") (name "Net-(Q8-E)") (class "Default")
      (node (ref "Q8") (pin "1") (pinfunction "E_1") (pintype "passive"))
      (node (ref "R97") (pin "1") (pinfunction "1_1") (pintype "passive"))
    )
    (net (code "159") (name "Net-(Q9-B)") (class "Default")
      (node (ref "D53") (pin "C") (pinfunction "C_C") (pintype "passive"))
      (node (ref "Q9") (pin "3") (pinfunction "B_3") (pintype "passive"))
      (node (ref "R125") (pin "1") (pinfunction "1_1") (pintype "passive"))
    )
    (net (code "160") (name "Net-(Q9-E)") (class "Default")
      (node (ref "Q9") (pin "1") (pinfunction "E_1") (pintype "passive"))
      (node (ref "R102") (pin "1") (pinfunction "1_1") (pintype "passive"))
      (node (ref "R115") (pin "1") (pinfunction "1_1") (pintype "passive"))
      (node (ref "R123") (pin "1") (pinfunction "1_1") (pintype "passive"))
    )
    (net (code "161") (name "Net-(Q10-B)") (class "Default")
      (node (ref "C56") (pin "1") (pinfunction "1_1") (pintype "passive"))
      (node (ref "Q10") (pin "3") (pinfunction "B_3") (pintype "passive"))
      (node (ref "R137") (pin "2") (pinfunction "2_2") (pintype "passive"))
      (node (ref "R138") (pin "1") (pinfunction "1_1") (pintype "passive"))
    )
    (net (code "162") (name "Net-(Q10-C)") (class "Default")
      (node (ref "D57") (pin "C") (pinfunction "C_C") (pintype "passive"))
      (node (ref "Q10") (pin "2") (pinfunction "C_2") (pintype "passive"))
    )
    (net (code "163") (name "Net-(Q10-E)") (class "Default")
      (node (ref "Q10") (pin "1") (pinfunction "E_1") (pintype "passive"))
      (node (ref "R139") (pin "2") (pinfunction "2_2") (pintype "passive"))
    )
    (net (code "164") (name "Net-(Q11-B)") (class "Default")
      (node (ref "C64") (pin "1") (pinfunction "1_1") (pintype "passive"))
      (node (ref "Q11") (pin "3") (pinfunction "B_3") (pintype "passive"))
      (node (ref "R142") (pin "2") (pinfunction "2_2") (pintype "passive"))
      (node (ref "R143") (pin "1") (pinfunction "1_1") (pintype "passive"))
    )
    (net (code "165") (name "Net-(Q11-C)") (class "Default")
      (node (ref "D58") (pin "C") (pinfunction "C_C") (pintype "passive"))
      (node (ref "Q11") (pin "2") (pinfunction "C_2") (pintype "passive"))
    )
    (net (code "166") (name "Net-(Q11-E)") (class "Default")
      (node (ref "Q11") (pin "1") (pinfunction "E_1") (pintype "passive"))
      (node (ref "R144") (pin "2") (pinfunction "2_2") (pintype "passive"))
    )
    (net (code "167") (name "Net-(R7-A)") (class "Default")
      (node (ref "C31") (pin "2") (pinfunction "2_2") (pintype "passive"))
      (node (ref "D2") (pin "A") (pinfunction "A_A") (pintype "passive"))
      (node (ref "D4") (pin "C") (pinfunction "C_C") (pintype "passive"))
      (node (ref "R7") (pin "1") (pinfunction "A_1") (pintype "passive"))
      (node (ref "R7") (pin "2") (pinfunction "S_2") (pintype "passive"))
      (node (ref "TR1") (pin "8") (pinfunction "3_8") (pintype "passive"))
    )
    (net (code "168") (name "Net-(R7-E)") (class "Default")
      (node (ref "R6") (pin "1") (pinfunction "1_1") (pintype "passive"))
      (node (ref "R7") (pin "3") (pinfunction "E_3") (pintype "passive"))
    )
    (net (code "169") (name "Net-(R9-A)") (class "Default")
      (node (ref "2K/1W") (pin "2") (pinfunction "2_2") (pintype "passive"))
      (node (ref "R9") (pin "1") (pinfunction "A_1") (pintype "passive"))
    )
    (net (code "170") (name "Net-(R19-A)") (class "Default")
      (node (ref "R19") (pin "1") (pinfunction "A_1") (pintype "passive"))
      (node (ref "R20") (pin "2") (pinfunction "2_2") (pintype "passive"))
    )
    (net (code "171") (name "Net-(R19-E)") (class "Default")
      (node (ref "R18") (pin "1") (pinfunction "1_1") (pintype "passive"))
      (node (ref "R19") (pin "3") (pinfunction "E_3") (pintype "passive"))
    )
    (net (code "172") (name "Net-(R19-S)") (class "Default")
      (node (ref "R16") (pin "1") (pinfunction "1_1") (pintype "passive"))
      (node (ref "R19") (pin "2") (pinfunction "S_2") (pintype "passive"))
    )
    (net (code "173") (name "Net-(R48-E)") (class "Default")
      (node (ref "R48") (pin "3") (pinfunction "E_3") (pintype "passive"))
      (node (ref "R49") (pin "1") (pinfunction "1_1") (pintype "passive"))
    )
    (net (code "174") (name "Net-(R48-S)") (class "Default")
      (node (ref "D27") (pin "C") (pinfunction "C_C") (pintype "passive"))
      (node (ref "R48") (pin "2") (pinfunction "S_2") (pintype "passive"))
    )
    (net (code "175") (name "Net-(R54-Pad1)") (class "Default")
      (node (ref "R54") (pin "1") (pinfunction "1_1") (pintype "passive"))
      (node (ref "R59") (pin "2") (pinfunction "2_2") (pintype "passive"))
      (node (ref "R60") (pin "2") (pinfunction "2_2") (pintype "passive"))
    )
    (net (code "176") (name "Net-(R55-Pad1)") (class "Default")
      (node (ref "R55") (pin "1") (pinfunction "1_1") (pintype "passive"))
      (node (ref "R57") (pin "1") (pinfunction "1_1") (pintype "passive"))
      (node (ref "R58") (pin "2") (pinfunction "2_2") (pintype "passive"))
    )
    (net (code "177") (name "Net-(R56-Pad1)") (class "Default")
      (node (ref "R56") (pin "1") (pinfunction "1_1") (pintype "passive"))
      (node (ref "R69") (pin "1") (pinfunction "1_1") (pintype "passive"))
    )
    (net (code "178") (name "Net-(R63-Pad1)") (class "Default")
      (node (ref "R63") (pin "1") (pinfunction "1_1") (pintype "passive"))
      (node (ref "R64") (pin "2") (pinfunction "2_2") (pintype "passive"))
    )
    (net (code "179") (name "Net-(R68-Pad1)") (class "Default")
      (node (ref "R68") (pin "1") (pinfunction "1_1") (pintype "passive"))
      (node (ref "R70") (pin "1") (pinfunction "1_1") (pintype "passive"))
      (node (ref "R71") (pin "2") (pinfunction "2_2") (pintype "passive"))
    )
    (net (code "180") (name "Net-(R74-Pad1)") (class "Default")
      (node (ref "R74") (pin "1") (pinfunction "1_1") (pintype "passive"))
      (node (ref "R75") (pin "2") (pinfunction "2_2") (pintype "passive"))
    )
    (net (code "181") (name "Net-(R81-A)") (class "Default")
      (node (ref "R78") (pin "2") (pinfunction "2_2") (pintype "passive"))
      (node (ref "R81") (pin "1") (pinfunction "A_1") (pintype "passive"))
    )
    (net (code "182") (name "Net-(R83-Pad1)") (class "Default")
      (node (ref "R83") (pin "1") (pinfunction "1_1") (pintype "passive"))
      (node (ref "R85") (pin "1") (pinfunction "1_1") (pintype "passive"))
      (node (ref "R86") (pin "2") (pinfunction "2_2") (pintype "passive"))
    )
    (net (code "183") (name "Net-(R94-E)") (class "Default")
      (node (ref "R94") (pin "3") (pinfunction "E_3") (pintype "passive"))
      (node (ref "R95") (pin "1") (pinfunction "1_1") (pintype "passive"))
    )
    (net (code "184") (name "Net-(R94-S)") (class "Default")
      (node (ref "D44") (pin "C") (pinfunction "C_C") (pintype "passive"))
      (node (ref "R94") (pin "2") (pinfunction "S_2") (pintype "passive"))
    )
    (net (code "185") (name "Net-(R100-Pad1)") (class "Default")
      (node (ref "R100") (pin "1") (pinfunction "1_1") (pintype "passive"))
      (node (ref "R105") (pin "2") (pinfunction "2_2") (pintype "passive"))
      (node (ref "R106") (pin "2") (pinfunction "2_2") (pintype "passive"))
    )
    (net (code "186") (name "Net-(R101-Pad1)") (class "Default")
      (node (ref "R101") (pin "1") (pinfunction "1_1") (pintype "passive"))
      (node (ref "R103") (pin "1") (pinfunction "1_1") (pintype "passive"))
      (node (ref "R104") (pin "2") (pinfunction "2_2") (pintype "passive"))
    )
    (net (code "187") (name "Net-(R109-Pad1)") (class "Default")
      (node (ref "R109") (pin "1") (pinfunction "1_1") (pintype "passive"))
      (node (ref "R110") (pin "2") (pinfunction "2_2") (pintype "passive"))
    )
    (net (code "188") (name "Net-(R114-Pad1)") (class "Default")
      (node (ref "R114") (pin "1") (pinfunction "1_1") (pintype "passive"))
      (node (ref "R116") (pin "1") (pinfunction "1_1") (pintype "passive"))
      (node (ref "R117") (pin "2") (pinfunction "2_2") (pintype "passive"))
    )
    (net (code "189") (name "Net-(R120-Pad1)") (class "Default")
      (node (ref "R120") (pin "1") (pinfunction "1_1") (pintype "passive"))
      (node (ref "R121") (pin "2") (pinfunction "2_2") (pintype "passive"))
    )
    (net (code "190") (name "Net-(R126-A)") (class "Default")
      (node (ref "R124") (pin "2") (pinfunction "2_2") (pintype "passive"))
      (node (ref "R126") (pin "1") (pinfunction "A_1") (pintype "passive"))
    )
    (net (code "191") (name "Net-(R129-Pad1)") (class "Default")
      (node (ref "R129") (pin "1") (pinfunction "1_1") (pintype "passive"))
      (node (ref "R131") (pin "1") (pinfunction "1_1") (pintype "passive"))
      (node (ref "R132") (pin "2") (pinfunction "2_2") (pintype "passive"))
    )
    (net (code "192") (name "Net-(R135-A)") (class "Default")
      (node (ref "R135") (pin "1") (pinfunction "A_1") (pintype "passive"))
      (node (ref "R136") (pin "2") (pinfunction "2_2") (pintype "passive"))
    )
    (net (code "193") (name "Net-(R135-S)") (class "Default")
      (node (ref "D57") (pin "A") (pinfunction "A_A") (pintype "passive"))
      (node (ref "R135") (pin "2") (pinfunction "S_2") (pintype "passive"))
    )
    (net (code "194") (name "Net-(R140-A)") (class "Default")
      (node (ref "R140") (pin "1") (pinfunction "A_1") (pintype "passive"))
      (node (ref "R141") (pin "2") (pinfunction "2_2") (pintype "passive"))
    )
    (net (code "195") (name "Net-(R140-S)") (class "Default")
      (node (ref "D58") (pin "A") (pinfunction "A_A") (pintype "passive"))
      (node (ref "R140") (pin "2") (pinfunction "S_2") (pintype "passive"))
    )
    (net (code "196") (name "Net-(R145-A)") (class "Default")
      (node (ref "R145") (pin "1") (pinfunction "A_1") (pintype "passive"))
      (node (ref "R148") (pin "1") (pinfunction "1_1") (pintype "passive"))
    )
    (net (code "197") (name "Net-(R145-E)") (class "Default")
      (node (ref "R145") (pin "3") (pinfunction "E_3") (pintype "passive"))
      (node (ref "R146") (pin "1") (pinfunction "1_1") (pintype "passive"))
    )
    (net (code "198") (name "Net-(R145-S)") (class "Default")
      (node (ref "R145") (pin "2") (pinfunction "S_2") (pintype "passive"))
      (node (ref "R147") (pin "2") (pinfunction "2_2") (pintype "passive"))
    )
    (net (code "199") (name "Net-(R160-A)") (class "Default")
      (node (ref "R160") (pin "1") (pinfunction "A_1") (pintype "passive"))
      (node (ref "R163") (pin "1") (pinfunction "1_1") (pintype "passive"))
    )
    (net (code "200") (name "Net-(R160-E)") (class "Default")
      (node (ref "R160") (pin "3") (pinfunction "E_3") (pintype "passive"))
      (node (ref "R161") (pin "1") (pinfunction "1_1") (pintype "passive"))
    )
    (net (code "201") (name "Net-(R160-S)") (class "Default")
      (node (ref "R160") (pin "2") (pinfunction "S_2") (pintype "passive"))
      (node (ref "R162") (pin "2") (pinfunction "2_2") (pintype "passive"))
    )
    (net (code "202") (name "Net-(T1-E)") (class "Default")
      (node (ref "R3") (pin "1") (pinfunction "1_1") (pintype "passive"))
      (node (ref "T1") (pin "1") (pinfunction "E_1") (pintype "passive"))
    )
    (net (code "203") (name "Net-(T2-B)") (class "Default")
      (node (ref "2K/1W1") (pin "1") (pinfunction "1_1") (pintype "passive"))
      (node (ref "T2") (pin "3") (pinfunction "B_3") (pintype "passive"))
    )
    (net (code "204") (name "Net-(T2-C)") (class "Default")
      (node (ref "2K/1W2") (pin "1") (pinfunction "1_1") (pintype "passive"))
      (node (ref "T2") (pin "2") (pinfunction "C_2") (pintype "passive"))
      (node (ref "T3") (pin "2") (pinfunction "C_2") (pintype "passive"))
    )
    (net (code "205") (name "Net-(T2-E)") (class "Default")
      (node (ref "D14") (pin "A") (pinfunction "A_A") (pintype "passive"))
      (node (ref "D7") (pin "C") (pinfunction "C_C") (pintype "passive"))
      (node (ref "R10") (pin "2") (pinfunction "2_2") (pintype "passive"))
      (node (ref "T2") (pin "1") (pinfunction "E_1") (pintype "passive"))
      (node (ref "T4") (pin "1") (pinfunction "E_1") (pintype "passive"))
    )
    (net (code "206") (name "Net-(T3-B)") (class "Default")
      (node (ref "2K/1W3") (pin "1") (pinfunction "1_1") (pintype "passive"))
      (node (ref "T3") (pin "3") (pinfunction "B_3") (pintype "passive"))
    )
    (net (code "207") (name "Net-(T4-B)") (class "Default")
      (node (ref "2K/1W4") (pin "1") (pinfunction "1_1") (pintype "passive"))
      (node (ref "T4") (pin "3") (pinfunction "B_3") (pintype "passive"))
    )
    (net (code "208") (name "Net-(T4-C)") (class "Default")
      (node (ref "2K/1W5") (pin "1") (pinfunction "1_1") (pintype "passive"))
      (node (ref "T4") (pin "2") (pinfunction "C_2") (pintype "passive"))
      (node (ref "T5") (pin "2") (pinfunction "C_2") (pintype "passive"))
    )
    (net (code "209") (name "Net-(T5-B)") (class "Default")
      (node (ref "2K/1W6") (pin "1") (pinfunction "1_1") (pintype "passive"))
      (node (ref "T5") (pin "3") (pinfunction "B_3") (pintype "passive"))
    )
    (net (code "210") (name "Net-(T6-B)") (class "Default")
      (node (ref "2K/1W7") (pin "1") (pinfunction "1_1") (pintype "passive"))
      (node (ref "T6") (pin "3") (pinfunction "B_3") (pintype "passive"))
    )
    (net (code "211") (name "Net-(T6-C)") (class "Default")
      (node (ref "2K/1W8") (pin "1") (pinfunction "1_1") (pintype "passive"))
      (node (ref "T6") (pin "2") (pinfunction "C_2") (pintype "passive"))
      (node (ref "T7") (pin "2") (pinfunction "C_2") (pintype "passive"))
    )
    (net (code "212") (name "Net-(T7-B)") (class "Default")
      (node (ref "2K/1W9") (pin "1") (pinfunction "1_1") (pintype "passive"))
      (node (ref "T7") (pin "3") (pinfunction "B_3") (pintype "passive"))
    )
    (net (code "213") (name "Net-(T7-E)") (class "Default")
      (node (ref "R8") (pin "1") (pinfunction "1_1") (pintype "passive"))
      (node (ref "T7") (pin "1") (pinfunction "E_1") (pintype "passive"))
      (node (ref "T9") (pin "1") (pinfunction "E_1") (pintype "passive"))
    )
    (net (code "214") (name "Net-(T8-B)") (class "Default")
      (node (ref "2K/1W10") (pin "1") (pinfunction "1_1") (pintype "passive"))
      (node (ref "T8") (pin "3") (pinfunction "B_3") (pintype "passive"))
    )
    (net (code "215") (name "Net-(T8-C)") (class "Default")
      (node (ref "2K/1W11") (pin "1") (pinfunction "1_1") (pintype "passive"))
      (node (ref "T8") (pin "2") (pinfunction "C_2") (pintype "passive"))
      (node (ref "T9") (pin "2") (pinfunction "C_2") (pintype "passive"))
    )
    (net (code "216") (name "Net-(T9-B)") (class "Default")
      (node (ref "2K/1W12") (pin "1") (pinfunction "1_1") (pintype "passive"))
      (node (ref "T9") (pin "3") (pinfunction "B_3") (pintype "passive"))
    )
    (net (code "217") (name "Net-(T10-B)") (class "Default")
      (node (ref "C43") (pin "1") (pinfunction "1_1") (pintype "passive"))
      (node (ref "D20") (pin "A") (pinfunction "A_A") (pintype "passive"))
      (node (ref "R35") (pin "2") (pinfunction "2_2") (pintype "passive"))
      (node (ref "R38") (pin "2") (pinfunction "2_2") (pintype "passive"))
      (node (ref "T10") (pin "3") (pinfunction "B_3") (pintype "passive"))
    )
    (net (code "218") (name "Net-(T10-E)") (class "Default")
      (node (ref "R37") (pin "2") (pinfunction "2_2") (pintype "passive"))
      (node (ref "T10") (pin "1") (pinfunction "E_1") (pintype "passive"))
      (node (ref "T11") (pin "1") (pinfunction "E_1") (pintype "passive"))
    )
    (net (code "219") (name "Net-(T11-B)") (class "Default")
      (node (ref "C44") (pin "2") (pinfunction "2_2") (pintype "passive"))
      (node (ref "D19") (pin "A") (pinfunction "A_A") (pintype "passive"))
      (node (ref "R36") (pin "1") (pinfunction "1_1") (pintype "passive"))
      (node (ref "R39") (pin "2") (pinfunction "2_2") (pintype "passive"))
      (node (ref "T11") (pin "3") (pinfunction "B_3") (pintype "passive"))
    )
    (net (code "220") (name "Net-(T11-C)") (class "Default")
      (node (ref "C43") (pin "2") (pinfunction "2_2") (pintype "passive"))
      (node (ref "D21") (pin "C") (pinfunction "C_C") (pintype "passive"))
      (node (ref "R33") (pin "2") (pinfunction "2_2") (pintype "passive"))
      (node (ref "R35") (pin "1") (pinfunction "1_1") (pintype "passive"))
      (node (ref "T11") (pin "2") (pinfunction "C_2") (pintype "passive"))
    )
    (net (code "221") (name "Net-(TR3-2)") (class "Default")
      (node (ref "D31") (pin "A") (pinfunction "A_A") (pintype "passive"))
      (node (ref "T12") (pin "A") (pinfunction "A_A") (pintype "passive"))
      (node (ref "TR3") (pin "7") (pinfunction "2_7") (pintype "passive"))
    )
    (net (code "222") (name "Net-(TR4-2)") (class "Default")
      (node (ref "D35") (pin "A") (pinfunction "A_A") (pintype "passive"))
      (node (ref "T13") (pin "A") (pinfunction "A_A") (pintype "passive"))
      (node (ref "TR4") (pin "7") (pinfunction "2_7") (pintype "passive"))
    )
    (net (code "223") (name "Net-(TR5-2)") (class "Default")
      (node (ref "D48") (pin "A") (pinfunction "A_A") (pintype "passive"))
      (node (ref "T14") (pin "A") (pinfunction "A_A") (pintype "passive"))
      (node (ref "TR5") (pin "7") (pinfunction "2_7") (pintype "passive"))
    )
    (net (code "224") (name "Net-(TR6-2)") (class "Default")
      (node (ref "D52") (pin "A") (pinfunction "A_A") (pintype "passive"))
      (node (ref "T15") (pin "A") (pinfunction "A_A") (pintype "passive"))
      (node (ref "TR6") (pin "7") (pinfunction "2_7") (pintype "passive"))
    )
    (net (code "225") (name "O") (class "Default")
      (node (ref "IC16") (pin "4") (pinfunction "O_4") (pintype "output"))
      (node (ref "IC19") (pin "4") (pinfunction "O_4") (pintype "output"))
    )
    (net (code "226") (name "PLN_NETRAL") (class "Default")
      (node (ref "TR1") (pin "4") (pinfunction "2_4") (pintype "passive"))
      (node (ref "TR2") (pin "4") (pinfunction "2_4") (pintype "passive"))
    )
    (net (code "227") (name "PLN_PHASE") (class "Default")
      (node (ref "TR1") (pin "1") (pinfunction "1_1") (pintype "passive"))
      (node (ref "TR2") (pin "1") (pinfunction "1_1") (pintype "passive"))
    )
    (net (code "228") (name "unconnected-(C47-Pad-)") (class "Default")
      (node (ref "C47") (pin "-") (pinfunction "-_-") (pintype "passive"))
    )
    (net (code "229") (name "unconnected-(C71-Pad2)") (class "Default")
      (node (ref "C71") (pin "2") (pinfunction "2_2") (pintype "passive"))
    )
    (net (code "230") (name "unconnected-(IC3-ON1-Pad1)") (class "Default")
      (node (ref "IC3") (pin "1") (pinfunction "ON1_1") (pintype "passive"))
    )
    (net (code "231") (name "unconnected-(IC3-ON2-Pad5)") (class "Default")
      (node (ref "IC3") (pin "5") (pinfunction "ON2_5") (pintype "passive"))
    )
    (net (code "232") (name "unconnected-(IC3-OPT-Pad8)") (class "Default")
      (node (ref "IC3") (pin "8") (pinfunction "OPT_8") (pintype "passive"))
    )
    (net (code "233") (name "unconnected-(IC4-ON1-Pad1)") (class "Default")
      (node (ref "IC4") (pin "1") (pinfunction "ON1_1") (pintype "passive"))
    )
    (net (code "234") (name "unconnected-(IC4-ON2-Pad5)") (class "Default")
      (node (ref "IC4") (pin "5") (pinfunction "ON2_5") (pintype "passive"))
    )
    (net (code "235") (name "unconnected-(IC4-OPT-Pad8)") (class "Default")
      (node (ref "IC4") (pin "8") (pinfunction "OPT_8") (pintype "passive"))
    )
    (net (code "236") (name "unconnected-(IC5-ON1-Pad1)") (class "Default")
      (node (ref "IC5") (pin "1") (pinfunction "ON1_1") (pintype "passive"))
    )
    (net (code "237") (name "unconnected-(IC5-ON2-Pad5)") (class "Default")
      (node (ref "IC5") (pin "5") (pinfunction "ON2_5") (pintype "passive"))
    )
    (net (code "238") (name "unconnected-(IC5-OPT-Pad8)") (class "Default")
      (node (ref "IC5") (pin "8") (pinfunction "OPT_8") (pintype "passive"))
    )
    (net (code "239") (name "unconnected-(IC6-ON1-Pad1)") (class "Default")
      (node (ref "IC6") (pin "1") (pinfunction "ON1_1") (pintype "passive"))
    )
    (net (code "240") (name "unconnected-(IC6-ON2-Pad5)") (class "Default")
      (node (ref "IC6") (pin "5") (pinfunction "ON2_5") (pintype "passive"))
    )
    (net (code "241") (name "unconnected-(IC6-OPT-Pad8)") (class "Default")
      (node (ref "IC6") (pin "8") (pinfunction "OPT_8") (pintype "passive"))
    )
    (net (code "242") (name "unconnected-(IC7-ON1-Pad1)") (class "Default")
      (node (ref "IC7") (pin "1") (pinfunction "ON1_1") (pintype "passive"))
    )
    (net (code "243") (name "unconnected-(IC7-ON2-Pad5)") (class "Default")
      (node (ref "IC7") (pin "5") (pinfunction "ON2_5") (pintype "passive"))
    )
    (net (code "244") (name "unconnected-(IC7-OPT-Pad8)") (class "Default")
      (node (ref "IC7") (pin "8") (pinfunction "OPT_8") (pintype "passive"))
    )
    (net (code "245") (name "unconnected-(IC8-ON1-Pad1)") (class "Default")
      (node (ref "IC8") (pin "1") (pinfunction "ON1_1") (pintype "passive"))
    )
    (net (code "246") (name "unconnected-(IC8-ON2-Pad5)") (class "Default")
      (node (ref "IC8") (pin "5") (pinfunction "ON2_5") (pintype "passive"))
    )
    (net (code "247") (name "unconnected-(IC8-OPT-Pad8)") (class "Default")
      (node (ref "IC8") (pin "8") (pinfunction "OPT_8") (pintype "passive"))
    )
    (net (code "248") (name "unconnected-(IC9-ON1-Pad1)") (class "Default")
      (node (ref "IC9") (pin "1") (pinfunction "ON1_1") (pintype "passive"))
    )
    (net (code "249") (name "unconnected-(IC9-ON2-Pad5)") (class "Default")
      (node (ref "IC9") (pin "5") (pinfunction "ON2_5") (pintype "passive"))
    )
    (net (code "250") (name "unconnected-(IC9-OPT-Pad8)") (class "Default")
      (node (ref "IC9") (pin "8") (pinfunction "OPT_8") (pintype "passive"))
    )
    (net (code "251") (name "unconnected-(IC10-ON1-Pad1)") (class "Default")
      (node (ref "IC10") (pin "1") (pinfunction "ON1_1") (pintype "passive"))
    )
    (net (code "252") (name "unconnected-(IC10-ON2-Pad5)") (class "Default")
      (node (ref "IC10") (pin "5") (pinfunction "ON2_5") (pintype "passive"))
    )
    (net (code "253") (name "unconnected-(IC10-OPT-Pad8)") (class "Default")
      (node (ref "IC10") (pin "8") (pinfunction "OPT_8") (pintype "passive"))
    )
    (net (code "254") (name "unconnected-(IC11-ON1-Pad1)") (class "Default")
      (node (ref "IC11") (pin "1") (pinfunction "ON1_1") (pintype "passive"))
    )
    (net (code "255") (name "unconnected-(IC11-ON2-Pad5)") (class "Default")
      (node (ref "IC11") (pin "5") (pinfunction "ON2_5") (pintype "passive"))
    )
    (net (code "256") (name "unconnected-(IC11-OPT-Pad8)") (class "Default")
      (node (ref "IC11") (pin "8") (pinfunction "OPT_8") (pintype "passive"))
    )
    (net (code "257") (name "unconnected-(IC12-ON1-Pad1)") (class "Default")
      (node (ref "IC12") (pin "1") (pinfunction "ON1_1") (pintype "passive"))
    )
    (net (code "258") (name "unconnected-(IC12-ON2-Pad5)") (class "Default")
      (node (ref "IC12") (pin "5") (pinfunction "ON2_5") (pintype "passive"))
    )
    (net (code "259") (name "unconnected-(IC12-OPT-Pad8)") (class "Default")
      (node (ref "IC12") (pin "8") (pinfunction "OPT_8") (pintype "passive"))
    )
    (net (code "260") (name "unconnected-(IC13-ON1-Pad1)") (class "Default")
      (node (ref "IC13") (pin "1") (pinfunction "ON1_1") (pintype "passive"))
    )
    (net (code "261") (name "unconnected-(IC13-ON2-Pad5)") (class "Default")
      (node (ref "IC13") (pin "5") (pinfunction "ON2_5") (pintype "passive"))
    )
    (net (code "262") (name "unconnected-(IC13-OPT-Pad8)") (class "Default")
      (node (ref "IC13") (pin "8") (pinfunction "OPT_8") (pintype "passive"))
    )
    (net (code "263") (name "unconnected-(IC14-ON1-Pad1)") (class "Default")
      (node (ref "IC14") (pin "1") (pinfunction "ON1_1") (pintype "passive"))
    )
    (net (code "264") (name "unconnected-(IC14-ON2-Pad5)") (class "Default")
      (node (ref "IC14") (pin "5") (pinfunction "ON2_5") (pintype "passive"))
    )
    (net (code "265") (name "unconnected-(IC14-OPT-Pad8)") (class "Default")
      (node (ref "IC14") (pin "8") (pinfunction "OPT_8") (pintype "passive"))
    )
    (net (code "266") (name "unconnected-(IC17-ON1-Pad1)") (class "Default")
      (node (ref "IC17") (pin "1") (pinfunction "ON1_1") (pintype "passive"))
    )
    (net (code "267") (name "unconnected-(IC17-ON2-Pad5)") (class "Default")
      (node (ref "IC17") (pin "5") (pinfunction "ON2_5") (pintype "passive"))
    )
    (net (code "268") (name "unconnected-(IC17-OPT-Pad8)") (class "Default")
      (node (ref "IC17") (pin "8") (pinfunction "OPT_8") (pintype "passive"))
    )
    (net (code "269") (name "unconnected-(T3-E-Pad1)") (class "Default")
      (node (ref "T3") (pin "1") (pinfunction "E_1") (pintype "passive"))
    )
    (net (code "270") (name "unconnected-(T5-E-Pad1)") (class "Default")
      (node (ref "T5") (pin "1") (pinfunction "E_1") (pintype "passive"))
    )
    (net (code "271") (name "unconnected-(T6-E-Pad1)") (class "Default")
      (node (ref "T6") (pin "1") (pinfunction "E_1") (pintype "passive"))
    )
    (net (code "272") (name "unconnected-(T8-E-Pad1)") (class "Default")
      (node (ref "T8") (pin "1") (pinfunction "E_1") (pintype "passive"))
    )
  )
)
